# elasticNode.net
KiCad netlist of a schematic drawn in EAGLE
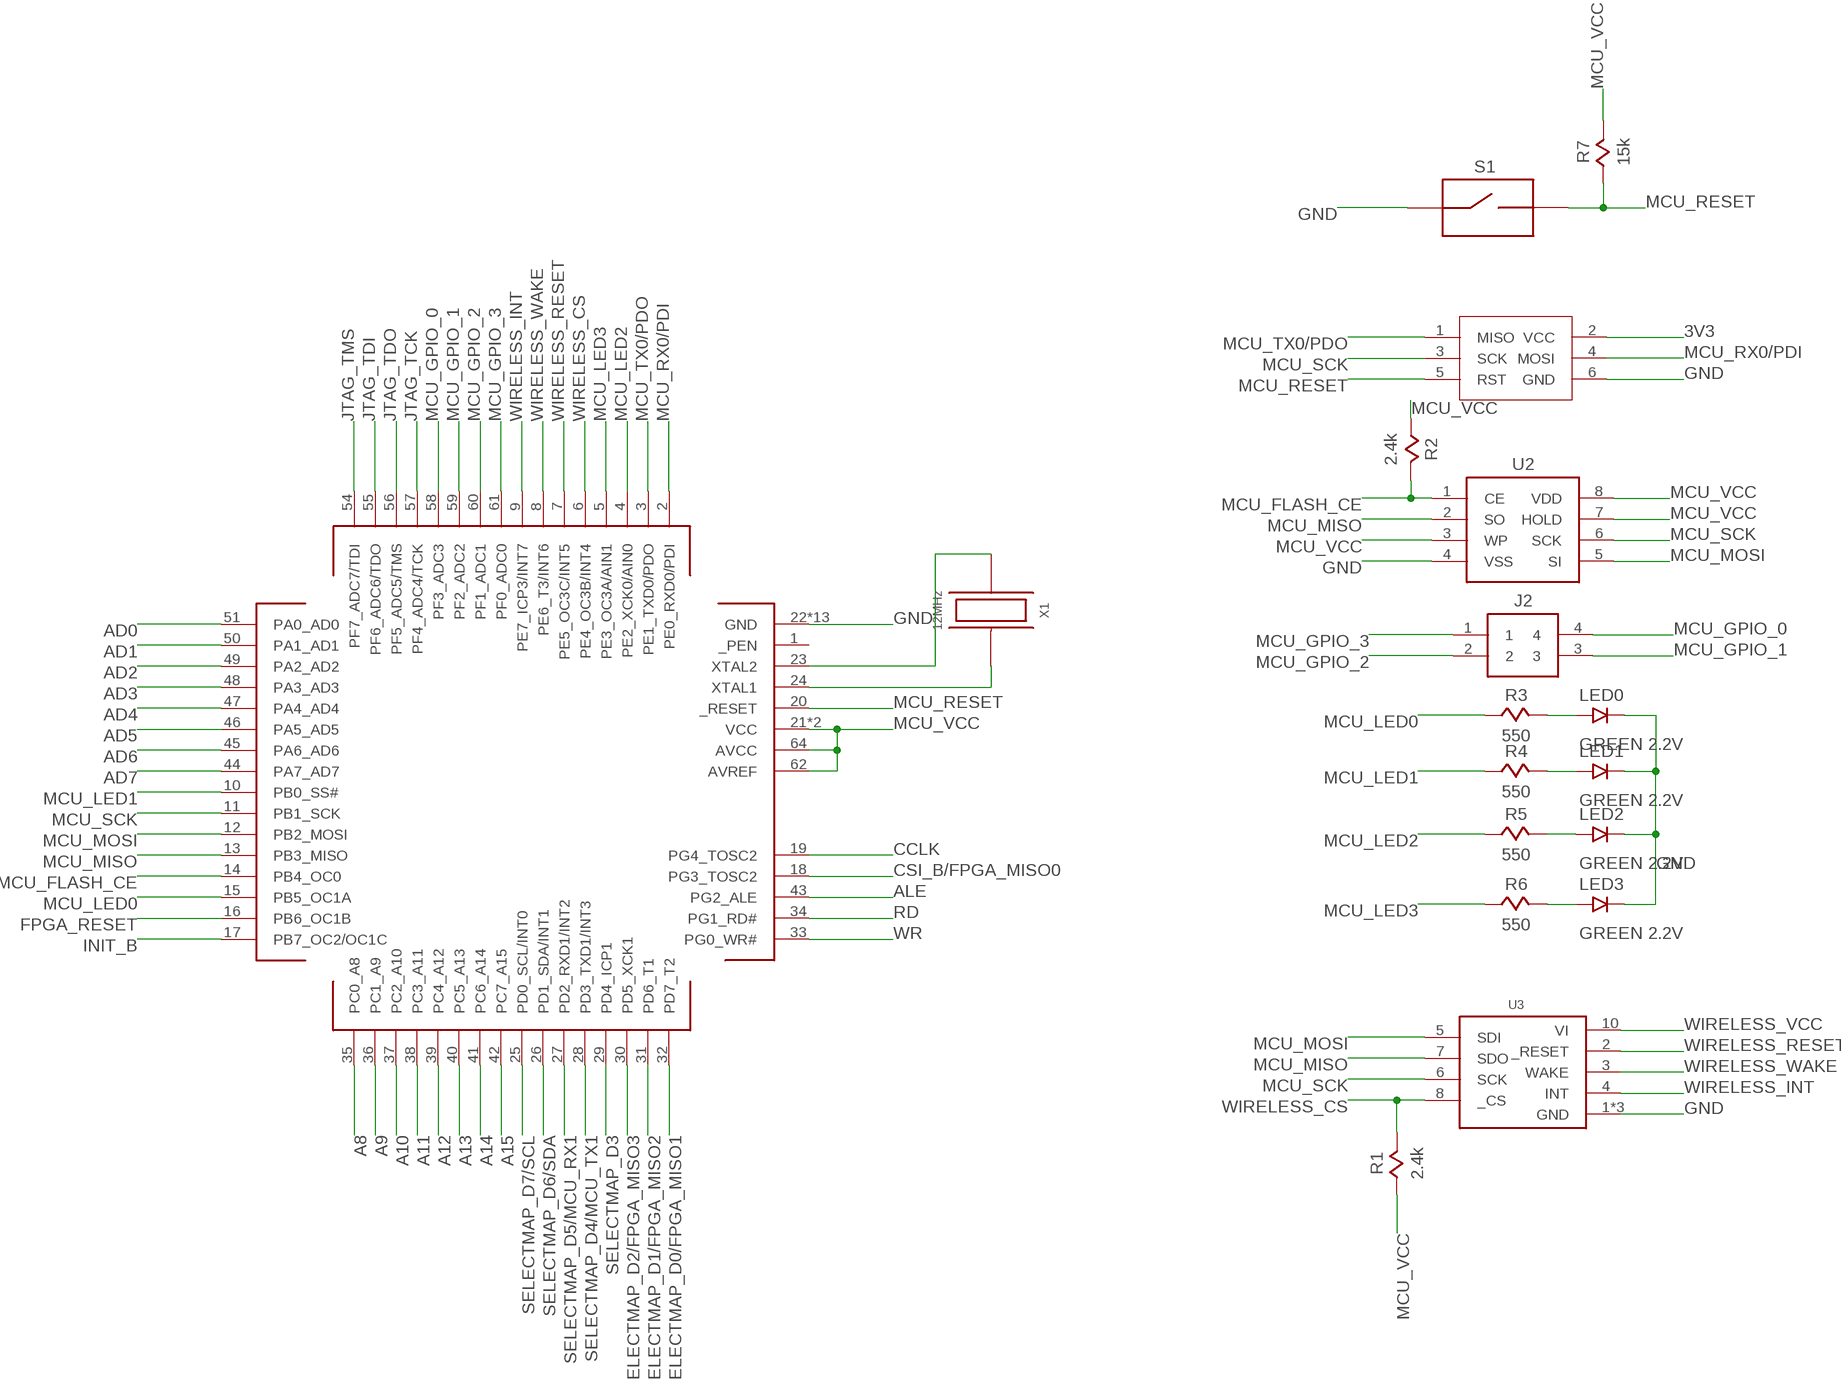
[diagram p0: schematic, sheet 1]
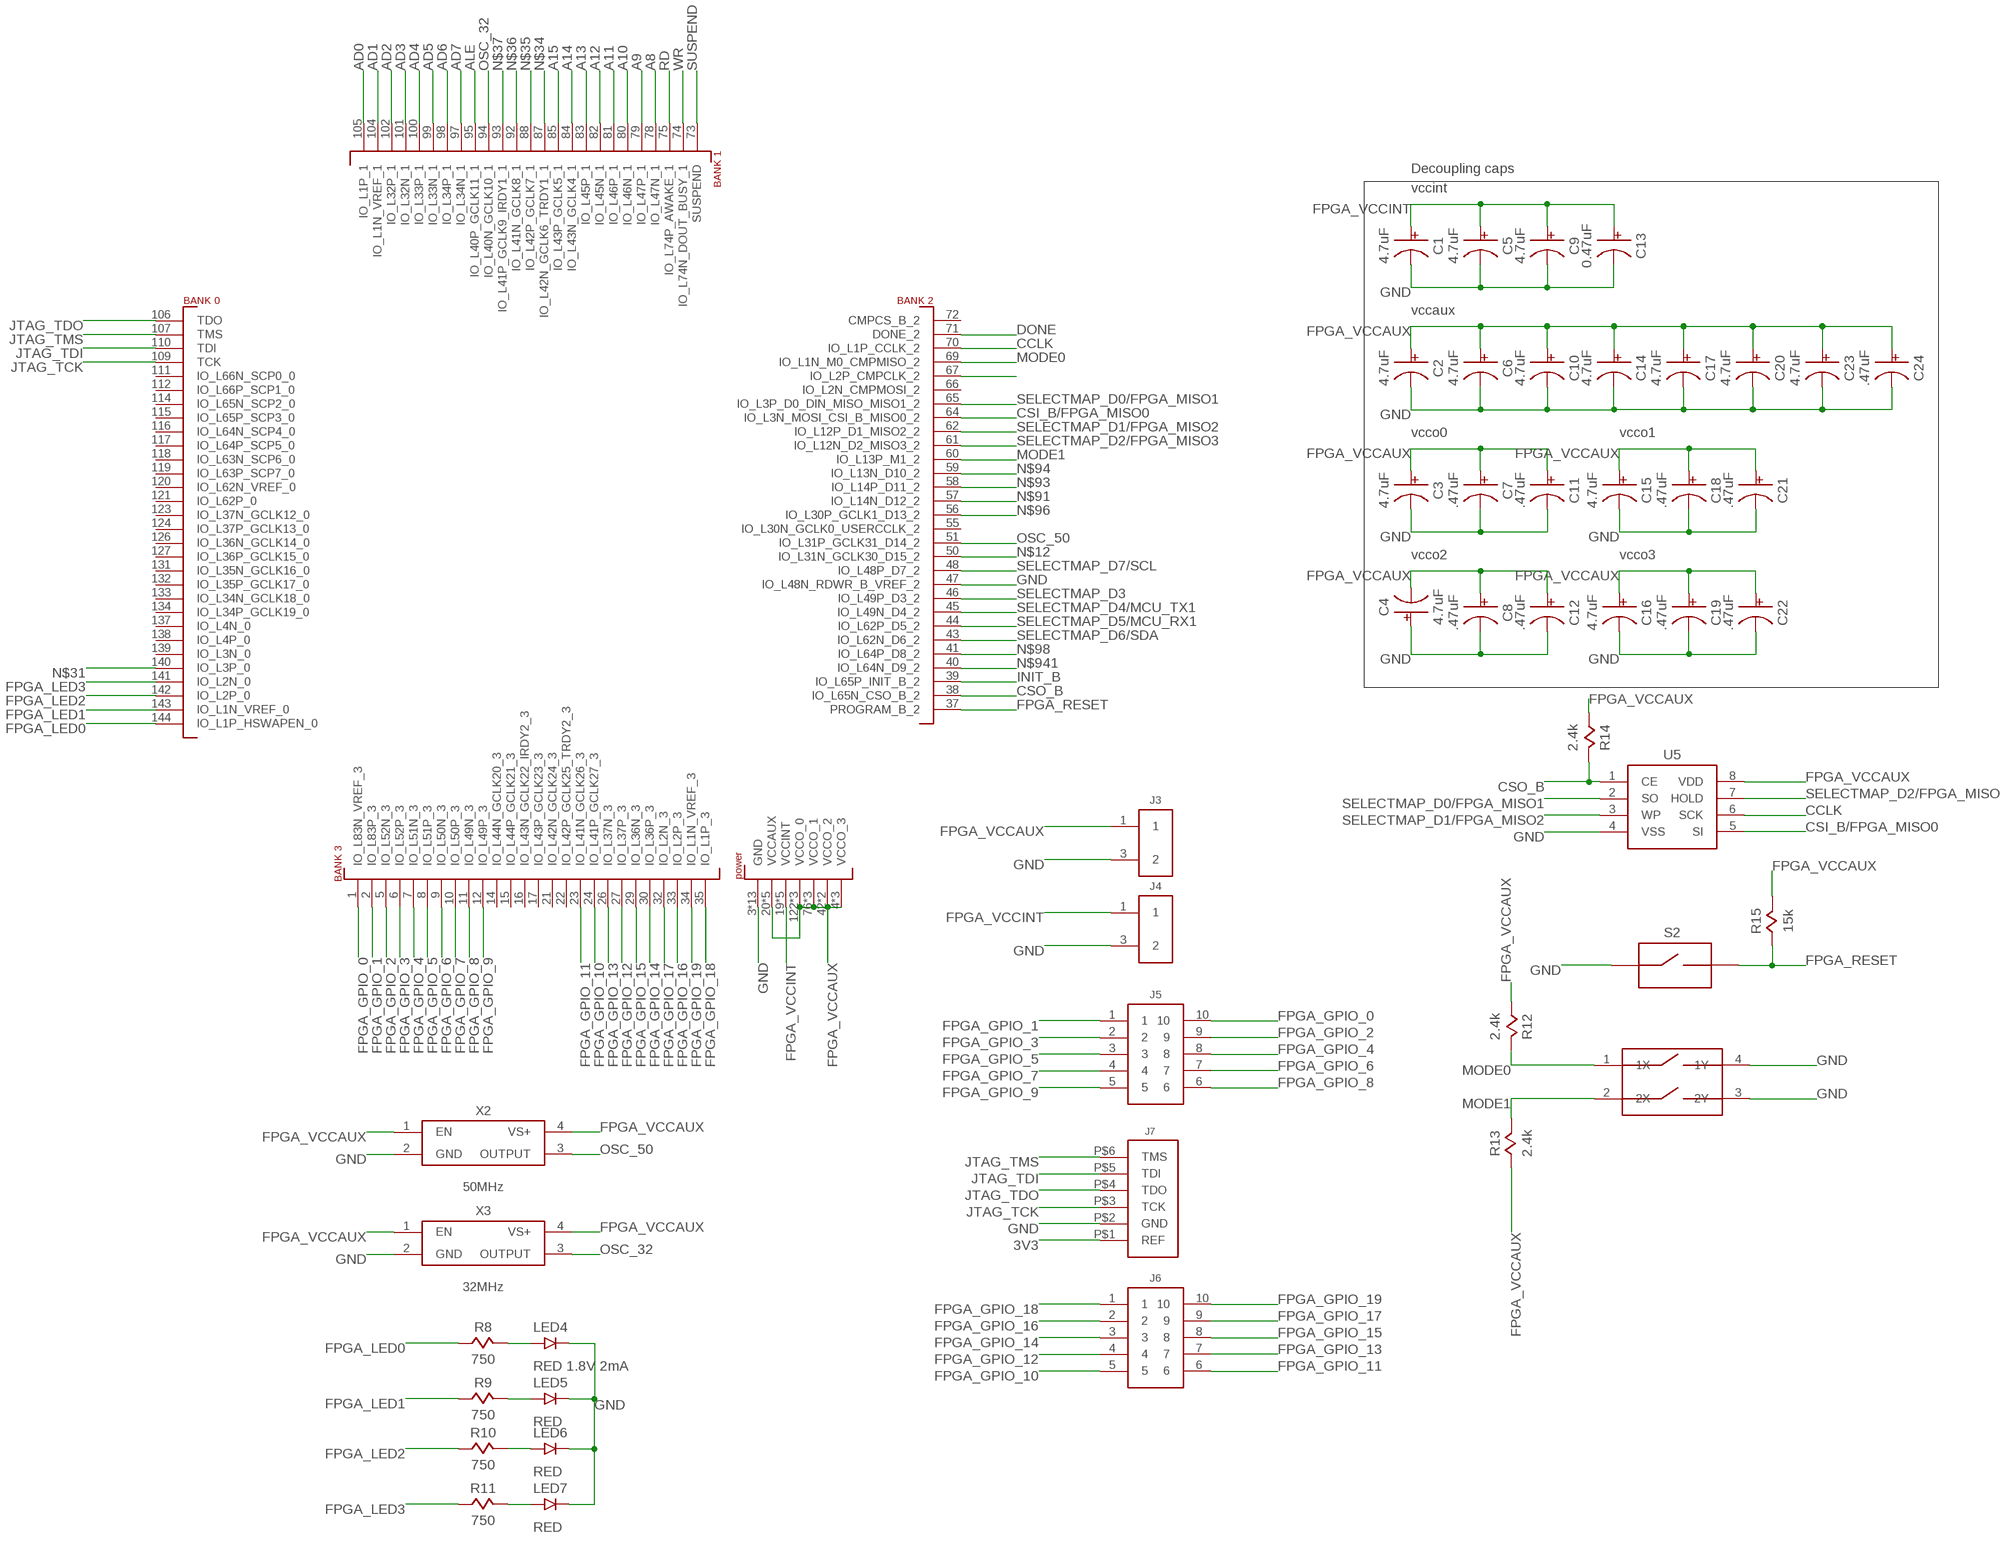
[diagram p1: schematic, sheet 2]
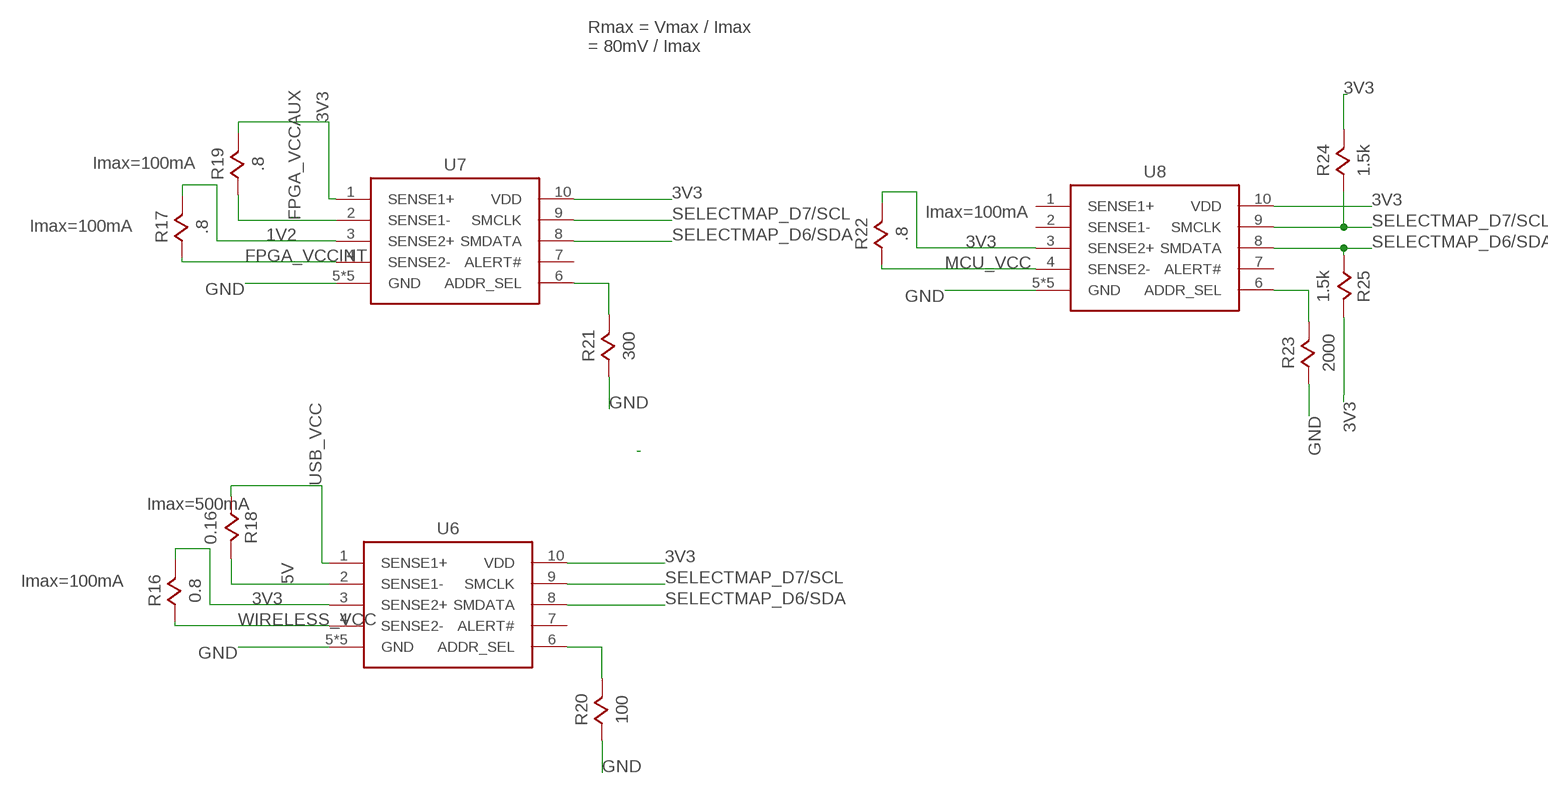
[diagram p2: schematic, sheet 3]
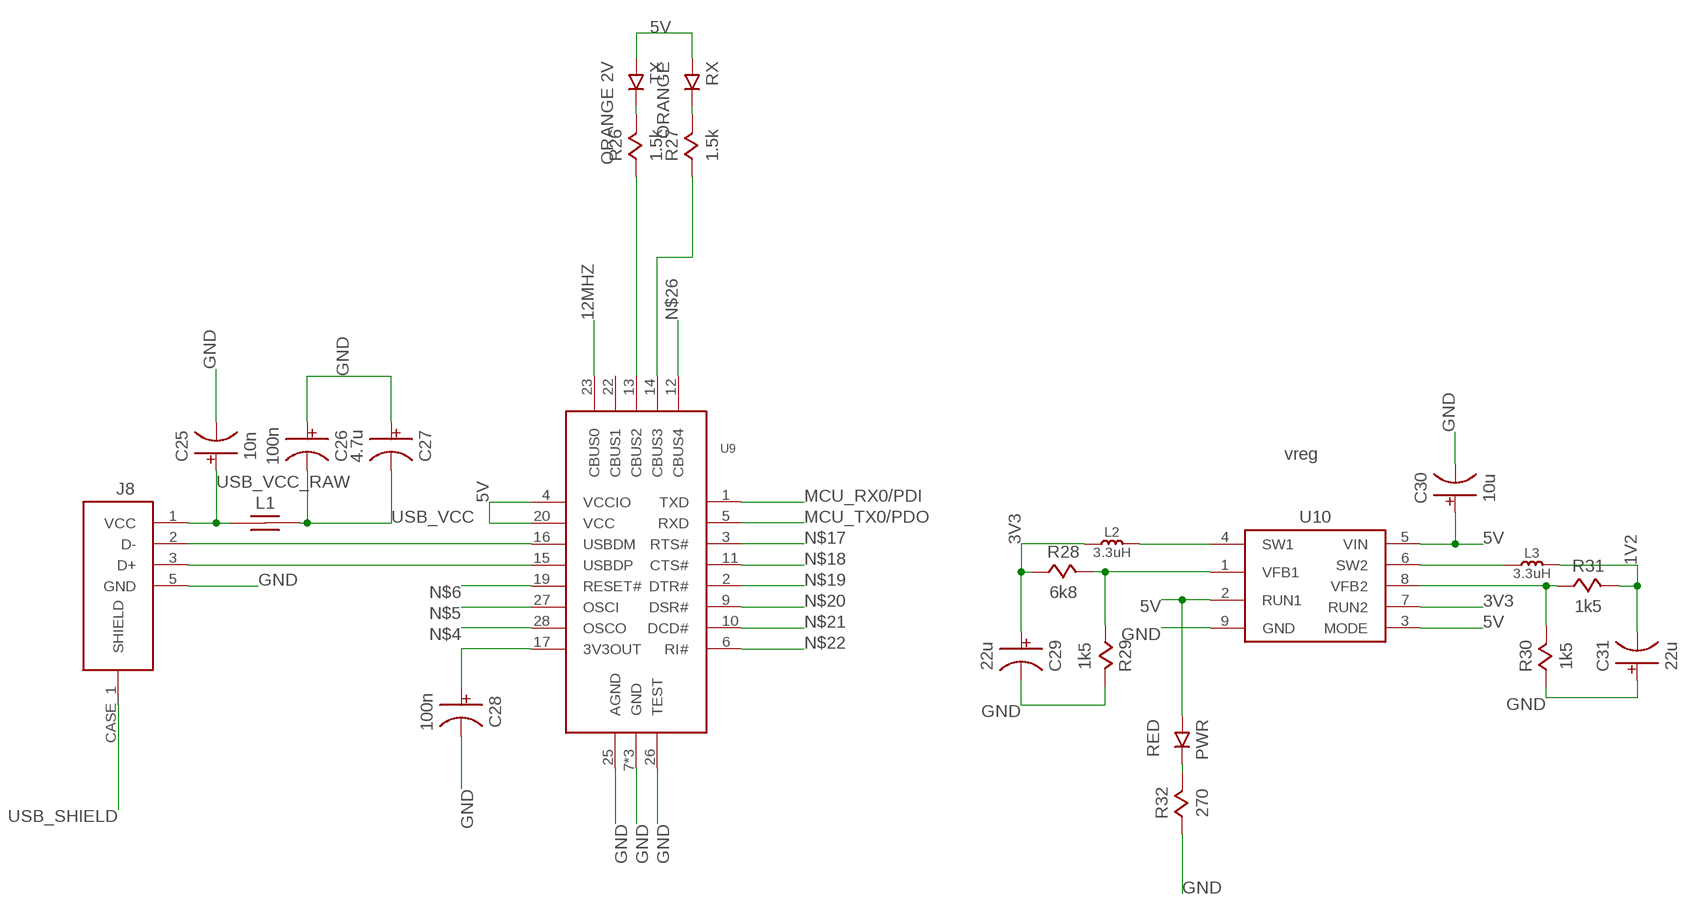
[diagram p3: schematic, sheet 4]

(export (version "E")
  (design (tool "Eeschema 10.0.6"))
  (components
    (comp (ref "R16")
      (value "0.8")
      (footprint "eagle-import:0805")
      (libsource (lib "eagle-import") (part "RESISTOR"))
    )
    (comp (ref "R17")
      (value ".8")
      (footprint "eagle-import:0805")
      (libsource (lib "eagle-import") (part "RESISTOR"))
    )
    (comp (ref "R18")
      (value "0.16")
      (footprint "eagle-import:0805")
      (libsource (lib "eagle-import") (part "RESISTOR"))
    )
    (comp (ref "R19")
      (value ".8")
      (footprint "eagle-import:0805")
      (libsource (lib "eagle-import") (part "RESISTOR"))
    )
    (comp (ref "R20")
      (value "100")
      (footprint "eagle-import:0805")
      (libsource (lib "eagle-import") (part "RESISTOR"))
    )
    (comp (ref "R21")
      (value "300")
      (footprint "eagle-import:0805")
      (libsource (lib "eagle-import") (part "RESISTOR"))
    )
    (comp (ref "R22")
      (value ".8")
      (footprint "eagle-import:0805")
      (libsource (lib "eagle-import") (part "RESISTOR"))
    )
    (comp (ref "R23")
      (value "2000")
      (footprint "eagle-import:0805")
      (libsource (lib "eagle-import") (part "RESISTOR"))
    )
    (comp (ref "R24")
      (value "1.5k")
      (footprint "eagle-import:0805")
      (libsource (lib "eagle-import") (part "RESISTOR"))
    )
    (comp (ref "R25")
      (value "1.5k")
      (footprint "eagle-import:0805")
      (libsource (lib "eagle-import") (part "RESISTOR"))
    )
    (comp (ref "U6")
      (value "PAC1720")
      (footprint "eagle-import:VDFN10")
      (libsource (lib "eagle-import") (part "PAC1720"))
    )
    (comp (ref "U7")
      (value "PAC1720")
      (footprint "eagle-import:VDFN10")
      (libsource (lib "eagle-import") (part "PAC1720"))
    )
    (comp (ref "U8")
      (value "PAC1720")
      (footprint "eagle-import:VDFN10")
      (libsource (lib "eagle-import") (part "PAC1720"))
    )
    (comp (ref "J1")
      (value "ISP_CONN_6PIN")
      (footprint "eagle-import:3X2_HEADER_SMT")
      (libsource (lib "eagle-import") (part "ISP_CONN_6PIN"))
    )
    (comp (ref "J2")
      (value "FEMALE_HEADER_2X2")
      (footprint "eagle-import:2X2_HEADER")
      (libsource (lib "eagle-import") (part "FEMALE_HEADER_2X2"))
    )
    (comp (ref "LED0")
      (value "GREEN 2.2V")
      (footprint "eagle-import:0805")
      (libsource (lib "eagle-import") (part "LED"))
    )
    (comp (ref "LED1")
      (value "GREEN 2.2V")
      (footprint "eagle-import:0805")
      (libsource (lib "eagle-import") (part "LED"))
    )
    (comp (ref "LED2")
      (value "GREEN 2.2V")
      (footprint "eagle-import:0805")
      (libsource (lib "eagle-import") (part "LED"))
    )
    (comp (ref "LED3")
      (value "GREEN 2.2V")
      (footprint "eagle-import:0805")
      (libsource (lib "eagle-import") (part "LED"))
    )
    (comp (ref "R1")
      (value "2.4k")
      (footprint "eagle-import:0805")
      (libsource (lib "eagle-import") (part "RESISTOR"))
    )
    (comp (ref "R2")
      (value "2.4k")
      (footprint "eagle-import:0805")
      (libsource (lib "eagle-import") (part "RESISTOR"))
    )
    (comp (ref "R3")
      (value "550")
      (footprint "eagle-import:0805")
      (libsource (lib "eagle-import") (part "RESISTOR"))
    )
    (comp (ref "R4")
      (value "550")
      (footprint "eagle-import:0805")
      (libsource (lib "eagle-import") (part "RESISTOR"))
    )
    (comp (ref "R5")
      (value "550")
      (footprint "eagle-import:0805")
      (libsource (lib "eagle-import") (part "RESISTOR"))
    )
    (comp (ref "R6")
      (value "550")
      (footprint "eagle-import:0805")
      (libsource (lib "eagle-import") (part "RESISTOR"))
    )
    (comp (ref "R7")
      (value "15k")
      (footprint "eagle-import:0805")
      (libsource (lib "eagle-import") (part "RESISTOR"))
    )
    (comp (ref "S1")
      (value "SPST_BUTTON2PIN_SMT")
      (footprint "eagle-import:SPST_2PIN_SMT")
      (libsource (lib "eagle-import") (part "SPST_BUTTON2PIN_SMT"))
    )
    (comp (ref "U1")
      (value "ATMEGA64AQFN")
      (footprint "eagle-import:QFN64")
      (libsource (lib "eagle-import") (part "ATMEGA64AQFN"))
    )
    (comp (ref "U2")
      (value "SST26VF032B")
      (footprint "eagle-import:SOIC8")
      (libsource (lib "eagle-import") (part "SST26VF032B"))
    )
    (comp (ref "U3")
      (value "MRF24J40MA")
      (footprint "eagle-import:MRF24J40MA")
      (libsource (lib "eagle-import") (part "MRF24J40MA"))
    )
    (comp (ref "X1")
      (value "12MHz")
      (footprint "eagle-import:3.2X2.5_OSC")
      (libsource (lib "eagle-import") (part "QUARTZ"))
    )
    (comp (ref "C25")
      (value "10n")
      (footprint "eagle-import:0805")
      (libsource (lib "eagle-import") (part "CAPACITOR0805"))
    )
    (comp (ref "C26")
      (value "100n")
      (footprint "eagle-import:0805")
      (libsource (lib "eagle-import") (part "CAPACITOR0805"))
    )
    (comp (ref "C27")
      (value "4.7u")
      (footprint "eagle-import:0805")
      (libsource (lib "eagle-import") (part "CAPACITOR0805"))
    )
    (comp (ref "C28")
      (value "100n")
      (footprint "eagle-import:0805")
      (libsource (lib "eagle-import") (part "CAPACITOR0805"))
    )
    (comp (ref "C29")
      (value "22u")
      (footprint "eagle-import:0805")
      (libsource (lib "eagle-import") (part "CAPACITOR0805"))
    )
    (comp (ref "C30")
      (value "10u")
      (footprint "eagle-import:0805")
      (libsource (lib "eagle-import") (part "CAPACITOR0805"))
    )
    (comp (ref "C31")
      (value "22u")
      (footprint "eagle-import:0805")
      (libsource (lib "eagle-import") (part "CAPACITOR0805"))
    )
    (comp (ref "J8")
      (value "USB_CONNSMT")
      (footprint "eagle-import:USB_MICRO_B_SMT")
      (libsource (lib "eagle-import") (part "USB_CONNSMT"))
    )
    (comp (ref "L1")
      (value "40Ohm 1.5A")
      (footprint "eagle-import:0805")
      (libsource (lib "eagle-import") (part "FERRITE_BEAD"))
    )
    (comp (ref "L2")
      (value "3.3uH")
      (footprint "eagle-import:0805")
      (libsource (lib "eagle-import") (part "INDUCTOR"))
    )
    (comp (ref "L3")
      (value "3.3uH")
      (footprint "eagle-import:0805")
      (libsource (lib "eagle-import") (part "INDUCTOR"))
    )
    (comp (ref "PWR")
      (value "RED")
      (footprint "eagle-import:0805")
      (libsource (lib "eagle-import") (part "LED"))
    )
    (comp (ref "R26")
      (value "1.5k")
      (footprint "eagle-import:0805")
      (libsource (lib "eagle-import") (part "RESISTOR"))
    )
    (comp (ref "R27")
      (value "1.5k")
      (footprint "eagle-import:0805")
      (libsource (lib "eagle-import") (part "RESISTOR"))
    )
    (comp (ref "R28")
      (value "6k8")
      (footprint "eagle-import:0805")
      (libsource (lib "eagle-import") (part "RESISTOR"))
    )
    (comp (ref "R29")
      (value "1k5")
      (footprint "eagle-import:0805")
      (libsource (lib "eagle-import") (part "RESISTOR"))
    )
    (comp (ref "R30")
      (value "1k5")
      (footprint "eagle-import:0805")
      (libsource (lib "eagle-import") (part "RESISTOR"))
    )
    (comp (ref "R31")
      (value "1k5")
      (footprint "eagle-import:0805")
      (libsource (lib "eagle-import") (part "RESISTOR"))
    )
    (comp (ref "R32")
      (value "270")
      (footprint "eagle-import:0805")
      (libsource (lib "eagle-import") (part "RESISTOR"))
    )
    (comp (ref "RX")
      (value "ORANGE")
      (footprint "eagle-import:0805")
      (libsource (lib "eagle-import") (part "LED"))
    )
    (comp (ref "TX")
      (value "ORANGE 2V")
      (footprint "eagle-import:0805")
      (libsource (lib "eagle-import") (part "LED"))
    )
    (comp (ref "U9")
      (value "FT232RSSOP28")
      (footprint "eagle-import:SSOP28")
      (libsource (lib "eagle-import") (part "FT232RSSOP28"))
    )
    (comp (ref "U10")
      (value "LTC3419DFN")
      (footprint "eagle-import:DFN8")
      (libsource (lib "eagle-import") (part "LTC3419DFN"))
    )
    (comp (ref "C1")
      (value "4.7uF")
      (footprint "eagle-import:0805")
      (libsource (lib "eagle-import") (part "CAPACITOR0805"))
    )
    (comp (ref "C2")
      (value "4.7uF")
      (footprint "eagle-import:0805")
      (libsource (lib "eagle-import") (part "CAPACITOR0805"))
    )
    (comp (ref "C3")
      (value "4.7uF")
      (footprint "eagle-import:0805")
      (libsource (lib "eagle-import") (part "CAPACITOR0805"))
    )
    (comp (ref "C4")
      (value "4.7uF")
      (footprint "eagle-import:0805")
      (libsource (lib "eagle-import") (part "CAPACITOR0805"))
    )
    (comp (ref "C5")
      (value "4.7uF")
      (footprint "eagle-import:0805")
      (libsource (lib "eagle-import") (part "CAPACITOR0805"))
    )
    (comp (ref "C6")
      (value "4.7uF")
      (footprint "eagle-import:0805")
      (libsource (lib "eagle-import") (part "CAPACITOR0805"))
    )
    (comp (ref "C7")
      (value ".47uF")
      (footprint "eagle-import:0402")
      (libsource (lib "eagle-import") (part "CAPACITOR0402"))
    )
    (comp (ref "C8")
      (value ".47uF")
      (footprint "eagle-import:0402")
      (libsource (lib "eagle-import") (part "CAPACITOR0402"))
    )
    (comp (ref "C9")
      (value "4.7uF")
      (footprint "eagle-import:0805")
      (libsource (lib "eagle-import") (part "CAPACITOR0805"))
    )
    (comp (ref "C10")
      (value "4.7uF")
      (footprint "eagle-import:0805")
      (libsource (lib "eagle-import") (part "CAPACITOR0805"))
    )
    (comp (ref "C11")
      (value ".47uF")
      (footprint "eagle-import:0402")
      (libsource (lib "eagle-import") (part "CAPACITOR0402"))
    )
    (comp (ref "C12")
      (value ".47uF")
      (footprint "eagle-import:0402")
      (libsource (lib "eagle-import") (part "CAPACITOR0402"))
    )
    (comp (ref "C13")
      (value "0.47uF")
      (footprint "eagle-import:0402")
      (libsource (lib "eagle-import") (part "CAPACITOR0402"))
    )
    (comp (ref "C14")
      (value "4.7uF")
      (footprint "eagle-import:0805")
      (libsource (lib "eagle-import") (part "CAPACITOR0805"))
    )
    (comp (ref "C15")
      (value "4.7uF")
      (footprint "eagle-import:0805")
      (libsource (lib "eagle-import") (part "CAPACITOR0805"))
    )
    (comp (ref "C16")
      (value "4.7uF")
      (footprint "eagle-import:0805")
      (libsource (lib "eagle-import") (part "CAPACITOR0805"))
    )
    (comp (ref "C17")
      (value "4.7uF")
      (footprint "eagle-import:0805")
      (libsource (lib "eagle-import") (part "CAPACITOR0805"))
    )
    (comp (ref "C18")
      (value ".47uF")
      (footprint "eagle-import:0402")
      (libsource (lib "eagle-import") (part "CAPACITOR0402"))
    )
    (comp (ref "C19")
      (value ".47uF")
      (footprint "eagle-import:0402")
      (libsource (lib "eagle-import") (part "CAPACITOR0402"))
    )
    (comp (ref "C20")
      (value "4.7uF")
      (footprint "eagle-import:0805")
      (libsource (lib "eagle-import") (part "CAPACITOR0805"))
    )
    (comp (ref "C21")
      (value ".47uF")
      (footprint "eagle-import:0402")
      (libsource (lib "eagle-import") (part "CAPACITOR0402"))
    )
    (comp (ref "C22")
      (value ".47uF")
      (footprint "eagle-import:0402")
      (libsource (lib "eagle-import") (part "CAPACITOR0402"))
    )
    (comp (ref "C23")
      (value "4.7uF")
      (footprint "eagle-import:0805")
      (libsource (lib "eagle-import") (part "CAPACITOR0805"))
    )
    (comp (ref "C24")
      (value ".47uF")
      (footprint "eagle-import:0805")
      (libsource (lib "eagle-import") (part "CAPACITOR0805"))
    )
    (comp (ref "J3")
      (value "FEMALE_HEADER_2X1")
      (footprint "eagle-import:2X1_HEADER")
      (libsource (lib "eagle-import") (part "FEMALE_HEADER_2X1"))
    )
    (comp (ref "J4")
      (value "FEMALE_HEADER_2X1")
      (footprint "eagle-import:2X1_HEADER")
      (libsource (lib "eagle-import") (part "FEMALE_HEADER_2X1"))
    )
    (comp (ref "J5")
      (value "FEMALE_HEADER_5X2")
      (footprint "eagle-import:5X2_HEADER")
      (libsource (lib "eagle-import") (part "FEMALE_HEADER_5X2"))
    )
    (comp (ref "J6")
      (value "FEMALE_HEADER_5X2")
      (footprint "eagle-import:5X2_HEADER")
      (libsource (lib "eagle-import") (part "FEMALE_HEADER_5X2"))
    )
    (comp (ref "J7")
      (value "JTAG_CONN_6PINTHT")
      (footprint "eagle-import:6X1_HEADER")
      (libsource (lib "eagle-import") (part "JTAG_CONN_6PINTHT"))
    )
    (comp (ref "LED4")
      (value "RED 1.8V 2mA")
      (footprint "eagle-import:0805")
      (libsource (lib "eagle-import") (part "LED"))
    )
    (comp (ref "LED5")
      (value "RED")
      (footprint "eagle-import:0805")
      (libsource (lib "eagle-import") (part "LED"))
    )
    (comp (ref "LED6")
      (value "RED")
      (footprint "eagle-import:0805")
      (libsource (lib "eagle-import") (part "LED"))
    )
    (comp (ref "LED7")
      (value "RED")
      (footprint "eagle-import:0805")
      (libsource (lib "eagle-import") (part "LED"))
    )
    (comp (ref "R8")
      (value "750")
      (footprint "eagle-import:0805")
      (libsource (lib "eagle-import") (part "RESISTOR"))
    )
    (comp (ref "R9")
      (value "750")
      (footprint "eagle-import:0805")
      (libsource (lib "eagle-import") (part "RESISTOR"))
    )
    (comp (ref "R10")
      (value "750")
      (footprint "eagle-import:0805")
      (libsource (lib "eagle-import") (part "RESISTOR"))
    )
    (comp (ref "R11")
      (value "750")
      (footprint "eagle-import:0805")
      (libsource (lib "eagle-import") (part "RESISTOR"))
    )
    (comp (ref "R12")
      (value "2.4k")
      (footprint "eagle-import:0805")
      (libsource (lib "eagle-import") (part "RESISTOR"))
    )
    (comp (ref "R13")
      (value "2.4k")
      (footprint "eagle-import:0805")
      (libsource (lib "eagle-import") (part "RESISTOR"))
    )
    (comp (ref "R14")
      (value "2.4k")
      (footprint "eagle-import:0805")
      (libsource (lib "eagle-import") (part "RESISTOR"))
    )
    (comp (ref "R15")
      (value "15k")
      (footprint "eagle-import:0805")
      (libsource (lib "eagle-import") (part "RESISTOR"))
    )
    (comp (ref "S2")
      (value "SPST_BUTTON2PIN_SMT")
      (footprint "eagle-import:SPST_2PIN_SMT")
      (libsource (lib "eagle-import") (part "SPST_BUTTON2PIN_SMT"))
    )
    (comp (ref "S3")
      (value "SPST_DIP_2SMT")
      (footprint "eagle-import:SPST_DIP2_SMT")
      (libsource (lib "eagle-import") (part "SPST_DIP_2SMT"))
    )
    (comp (ref "U4")
      (value "SPARTAN6-LX9")
      (footprint "eagle-import:TQG144")
      (libsource (lib "eagle-import") (part "SPARTAN6-LX9"))
    )
    (comp (ref "U5")
      (value "SST26VF032B")
      (footprint "eagle-import:SOIC8")
      (libsource (lib "eagle-import") (part "SST26VF032B"))
    )
    (comp (ref "X2")
      (value "50MHz")
      (footprint "eagle-import:3.2X2.5_OSC")
      (libsource (lib "eagle-import") (part "OSCILLATOR3.2X2.5"))
    )
    (comp (ref "X3")
      (value "32MHz")
      (footprint "eagle-import:3.2X2.5_OSC")
      (libsource (lib "eagle-import") (part "OSCILLATOR3.2X2.5"))
    )
  )
  (nets
    (net (code "1") (name "1V2") (class "Default")
      (node (ref "C31") (pin "2") (pinfunction "P$2_2") (pintype "bidirectional"))
      (node (ref "L3") (pin "2") (pinfunction "P$2_2") (pintype "bidirectional"))
      (node (ref "R17") (pin "2") (pinfunction "2_2") (pintype "bidirectional"))
      (node (ref "R31") (pin "2") (pinfunction "2_2") (pintype "bidirectional"))
      (node (ref "U7") (pin "3") (pinfunction "SENSE2+_3") (pintype "bidirectional"))
    )
    (net (code "2") (name "3V3") (class "Default")
      (node (ref "C29") (pin "1") (pinfunction "P$1_1") (pintype "bidirectional"))
      (node (ref "J1") (pin "2") (pinfunction "VCC_2") (pintype "bidirectional"))
      (node (ref "J7") (pin "P$1") (pinfunction "REF_P$1") (pintype "bidirectional"))
      (node (ref "L2") (pin "1") (pinfunction "P$1_1") (pintype "bidirectional"))
      (node (ref "R16") (pin "2") (pinfunction "2_2") (pintype "bidirectional"))
      (node (ref "R19") (pin "2") (pinfunction "2_2") (pintype "bidirectional"))
      (node (ref "R22") (pin "2") (pinfunction "2_2") (pintype "bidirectional"))
      (node (ref "R24") (pin "2") (pinfunction "2_2") (pintype "bidirectional"))
      (node (ref "R25") (pin "2") (pinfunction "2_2") (pintype "bidirectional"))
      (node (ref "R28") (pin "1") (pinfunction "1_1") (pintype "bidirectional"))
      (node (ref "U10") (pin "7") (pinfunction "RUN2_7") (pintype "bidirectional"))
      (node (ref "U6") (pin "10") (pinfunction "VDD_10") (pintype "bidirectional"))
      (node (ref "U6") (pin "3") (pinfunction "SENSE2+_3") (pintype "bidirectional"))
      (node (ref "U7") (pin "1") (pinfunction "SENSE1+_1") (pintype "bidirectional"))
      (node (ref "U7") (pin "10") (pinfunction "VDD_10") (pintype "bidirectional"))
      (node (ref "U8") (pin "10") (pinfunction "VDD_10") (pintype "bidirectional"))
      (node (ref "U8") (pin "3") (pinfunction "SENSE2+_3") (pintype "bidirectional"))
    )
    (net (code "3") (name "5V") (class "Default")
      (node (ref "C30") (pin "1") (pinfunction "P$1_1") (pintype "bidirectional"))
      (node (ref "PWR") (pin "1") (pinfunction "1_1") (pintype "bidirectional"))
      (node (ref "R18") (pin "2") (pinfunction "2_2") (pintype "bidirectional"))
      (node (ref "RX") (pin "1") (pinfunction "1_1") (pintype "bidirectional"))
      (node (ref "TX") (pin "1") (pinfunction "1_1") (pintype "bidirectional"))
      (node (ref "U10") (pin "2") (pinfunction "RUN1_2") (pintype "bidirectional"))
      (node (ref "U10") (pin "3") (pinfunction "MODE_3") (pintype "bidirectional"))
      (node (ref "U10") (pin "5") (pinfunction "VIN_5") (pintype "bidirectional"))
      (node (ref "U6") (pin "2") (pinfunction "SENSE1-_2") (pintype "bidirectional"))
      (node (ref "U9") (pin "20") (pinfunction "VCC_20") (pintype "bidirectional"))
      (node (ref "U9") (pin "4") (pinfunction "VCCIO_4") (pintype "bidirectional"))
    )
    (net (code "4") (name "12MHZ") (class "Default")
      (node (ref "U9") (pin "23") (pinfunction "CBUS0_23") (pintype "bidirectional"))
    )
    (net (code "5") (name "A8") (class "Default")
      (node (ref "U1") (pin "35") (pinfunction "PC0_A8_35") (pintype "bidirectional"))
      (node (ref "U4") (pin "78") (pinfunction "IO_L47N_1_78") (pintype "bidirectional"))
    )
    (net (code "6") (name "A9") (class "Default")
      (node (ref "U1") (pin "36") (pinfunction "PC1_A9_36") (pintype "bidirectional"))
      (node (ref "U4") (pin "79") (pinfunction "IO_L47P_1_79") (pintype "bidirectional"))
    )
    (net (code "7") (name "A10") (class "Default")
      (node (ref "U1") (pin "37") (pinfunction "PC2_A10_37") (pintype "bidirectional"))
      (node (ref "U4") (pin "80") (pinfunction "IO_L46N_1_80") (pintype "bidirectional"))
    )
    (net (code "8") (name "A11") (class "Default")
      (node (ref "U1") (pin "38") (pinfunction "PC3_A11_38") (pintype "bidirectional"))
      (node (ref "U4") (pin "81") (pinfunction "IO_L46P_1_81") (pintype "bidirectional"))
    )
    (net (code "9") (name "A12") (class "Default")
      (node (ref "U1") (pin "39") (pinfunction "PC4_A12_39") (pintype "bidirectional"))
      (node (ref "U4") (pin "82") (pinfunction "IO_L45N_1_82") (pintype "bidirectional"))
    )
    (net (code "10") (name "A13") (class "Default")
      (node (ref "U1") (pin "40") (pinfunction "PC5_A13_40") (pintype "bidirectional"))
      (node (ref "U4") (pin "83") (pinfunction "IO_L45P_1_83") (pintype "bidirectional"))
    )
    (net (code "11") (name "A14") (class "Default")
      (node (ref "U1") (pin "41") (pinfunction "PC6_A14_41") (pintype "bidirectional"))
      (node (ref "U4") (pin "84") (pinfunction "IO_L43N_GCLK4_1_84") (pintype "bidirectional"))
    )
    (net (code "12") (name "A15") (class "Default")
      (node (ref "U1") (pin "42") (pinfunction "PC7_A15_42") (pintype "bidirectional"))
      (node (ref "U4") (pin "85") (pinfunction "IO_L43P_GCLK5_1_85") (pintype "bidirectional"))
    )
    (net (code "13") (name "AD0") (class "Default")
      (node (ref "U1") (pin "51") (pinfunction "PA0_AD0_51") (pintype "bidirectional"))
      (node (ref "U4") (pin "105") (pinfunction "IO_L1P_1_105") (pintype "bidirectional"))
    )
    (net (code "14") (name "AD1") (class "Default")
      (node (ref "U1") (pin "50") (pinfunction "PA1_AD1_50") (pintype "bidirectional"))
      (node (ref "U4") (pin "104") (pinfunction "IO_L1N_VREF_1_104") (pintype "bidirectional"))
    )
    (net (code "15") (name "AD2") (class "Default")
      (node (ref "U1") (pin "49") (pinfunction "PA2_AD2_49") (pintype "bidirectional"))
      (node (ref "U4") (pin "102") (pinfunction "IO_L32P_1_102") (pintype "bidirectional"))
    )
    (net (code "16") (name "AD3") (class "Default")
      (node (ref "U1") (pin "48") (pinfunction "PA3_AD3_48") (pintype "bidirectional"))
      (node (ref "U4") (pin "101") (pinfunction "IO_L32N_1_101") (pintype "bidirectional"))
    )
    (net (code "17") (name "AD4") (class "Default")
      (node (ref "U1") (pin "47") (pinfunction "PA4_AD4_47") (pintype "bidirectional"))
      (node (ref "U4") (pin "100") (pinfunction "IO_L33P_1_100") (pintype "bidirectional"))
    )
    (net (code "18") (name "AD5") (class "Default")
      (node (ref "U1") (pin "46") (pinfunction "PA5_AD5_46") (pintype "bidirectional"))
      (node (ref "U4") (pin "99") (pinfunction "IO_L33N_1_99") (pintype "bidirectional"))
    )
    (net (code "19") (name "AD6") (class "Default")
      (node (ref "U1") (pin "45") (pinfunction "PA6_AD6_45") (pintype "bidirectional"))
      (node (ref "U4") (pin "98") (pinfunction "IO_L34P_1_98") (pintype "bidirectional"))
    )
    (net (code "20") (name "AD7") (class "Default")
      (node (ref "U1") (pin "44") (pinfunction "PA7_AD7_44") (pintype "bidirectional"))
      (node (ref "U4") (pin "97") (pinfunction "IO_L34N_1_97") (pintype "bidirectional"))
    )
    (net (code "21") (name "ALE") (class "Default")
      (node (ref "U1") (pin "43") (pinfunction "PG2_ALE_43") (pintype "bidirectional"))
      (node (ref "U4") (pin "95") (pinfunction "IO_L40P_GCLK11_1_95") (pintype "bidirectional"))
    )
    (net (code "22") (name "CCLK") (class "Default")
      (node (ref "U1") (pin "19") (pinfunction "PG4_TOSC2_19") (pintype "bidirectional"))
      (node (ref "U4") (pin "70") (pinfunction "IO_L1P_CCLK_2_70") (pintype "bidirectional"))
      (node (ref "U5") (pin "6") (pinfunction "SCK_6") (pintype "bidirectional"))
    )
    (net (code "23") (name "CSI_B{slash}FPGA_MISO0") (class "Default")
      (node (ref "U1") (pin "18") (pinfunction "PG3_TOSC2_18") (pintype "bidirectional"))
      (node (ref "U4") (pin "64") (pinfunction "IO_L3N_MOSI_CSI_B_MISO0_2_64") (pintype "bidirectional"))
      (node (ref "U5") (pin "5") (pinfunction "SI_5") (pintype "bidirectional"))
    )
    (net (code "24") (name "CSO_B") (class "Default")
      (node (ref "R14") (pin "2") (pinfunction "2_2") (pintype "bidirectional"))
      (node (ref "U4") (pin "38") (pinfunction "IO_L65N_CSO_B_2_38") (pintype "bidirectional"))
      (node (ref "U5") (pin "1") (pinfunction "CE_1") (pintype "bidirectional"))
    )
    (net (code "25") (name "DONE") (class "Default")
      (node (ref "U4") (pin "71") (pinfunction "DONE_2_71") (pintype "bidirectional"))
    )
    (net (code "26") (name "FPGA_GPIO_0") (class "Default")
      (node (ref "J5") (pin "10") (pinfunction "10_10") (pintype "bidirectional"))
      (node (ref "U4") (pin "1") (pinfunction "IO_L83N_VREF_3_1") (pintype "bidirectional"))
    )
    (net (code "27") (name "FPGA_GPIO_1") (class "Default")
      (node (ref "J5") (pin "1") (pinfunction "1_1") (pintype "bidirectional"))
      (node (ref "U4") (pin "2") (pinfunction "IO_L83P_3_2") (pintype "bidirectional"))
    )
    (net (code "28") (name "FPGA_GPIO_2") (class "Default")
      (node (ref "J5") (pin "9") (pinfunction "9_9") (pintype "bidirectional"))
      (node (ref "U4") (pin "5") (pinfunction "IO_L52N_3_5") (pintype "bidirectional"))
    )
    (net (code "29") (name "FPGA_GPIO_3") (class "Default")
      (node (ref "J5") (pin "2") (pinfunction "2_2") (pintype "bidirectional"))
      (node (ref "U4") (pin "6") (pinfunction "IO_L52P_3_6") (pintype "bidirectional"))
    )
    (net (code "30") (name "FPGA_GPIO_4") (class "Default")
      (node (ref "J5") (pin "8") (pinfunction "8_8") (pintype "bidirectional"))
      (node (ref "U4") (pin "7") (pinfunction "IO_L51N_3_7") (pintype "bidirectional"))
    )
    (net (code "31") (name "FPGA_GPIO_5") (class "Default")
      (node (ref "J5") (pin "3") (pinfunction "3_3") (pintype "bidirectional"))
      (node (ref "U4") (pin "8") (pinfunction "IO_L51P_3_8") (pintype "bidirectional"))
    )
    (net (code "32") (name "FPGA_GPIO_6") (class "Default")
      (node (ref "J5") (pin "7") (pinfunction "7_7") (pintype "bidirectional"))
      (node (ref "U4") (pin "9") (pinfunction "IO_L50N_3_9") (pintype "bidirectional"))
    )
    (net (code "33") (name "FPGA_GPIO_7") (class "Default")
      (node (ref "J5") (pin "4") (pinfunction "4_4") (pintype "bidirectional"))
      (node (ref "U4") (pin "10") (pinfunction "IO_L50P_3_10") (pintype "bidirectional"))
    )
    (net (code "34") (name "FPGA_GPIO_8") (class "Default")
      (node (ref "J5") (pin "6") (pinfunction "6_6") (pintype "bidirectional"))
      (node (ref "U4") (pin "11") (pinfunction "IO_L49N_3_11") (pintype "bidirectional"))
    )
    (net (code "35") (name "FPGA_GPIO_9") (class "Default")
      (node (ref "J5") (pin "5") (pinfunction "5_5") (pintype "bidirectional"))
      (node (ref "U4") (pin "12") (pinfunction "IO_L49P_3_12") (pintype "bidirectional"))
    )
    (net (code "36") (name "FPGA_GPIO_10") (class "Default")
      (node (ref "J6") (pin "5") (pinfunction "5_5") (pintype "bidirectional"))
      (node (ref "U4") (pin "24") (pinfunction "IO_L41P_GCLK27_3_24") (pintype "bidirectional"))
    )
    (net (code "37") (name "FPGA_GPIO_11") (class "Default")
      (node (ref "J6") (pin "6") (pinfunction "6_6") (pintype "bidirectional"))
      (node (ref "U4") (pin "23") (pinfunction "IO_L41N_GCLK26_3_23") (pintype "bidirectional"))
    )
    (net (code "38") (name "FPGA_GPIO_12") (class "Default")
      (node (ref "J6") (pin "4") (pinfunction "4_4") (pintype "bidirectional"))
      (node (ref "U4") (pin "27") (pinfunction "IO_L37P_3_27") (pintype "bidirectional"))
    )
    (net (code "39") (name "FPGA_GPIO_13") (class "Default")
      (node (ref "J6") (pin "7") (pinfunction "7_7") (pintype "bidirectional"))
      (node (ref "U4") (pin "26") (pinfunction "IO_L37N_3_26") (pintype "bidirectional"))
    )
    (net (code "40") (name "FPGA_GPIO_14") (class "Default")
      (node (ref "J6") (pin "3") (pinfunction "3_3") (pintype "bidirectional"))
      (node (ref "U4") (pin "30") (pinfunction "IO_L36P_3_30") (pintype "bidirectional"))
    )
    (net (code "41") (name "FPGA_GPIO_15") (class "Default")
      (node (ref "J6") (pin "8") (pinfunction "8_8") (pintype "bidirectional"))
      (node (ref "U4") (pin "29") (pinfunction "IO_L36N_3_29") (pintype "bidirectional"))
    )
    (net (code "42") (name "FPGA_GPIO_16") (class "Default")
      (node (ref "J6") (pin "2") (pinfunction "2_2") (pintype "bidirectional"))
      (node (ref "U4") (pin "33") (pinfunction "IO_L2P_3_33") (pintype "bidirectional"))
    )
    (net (code "43") (name "FPGA_GPIO_17") (class "Default")
      (node (ref "J6") (pin "9") (pinfunction "9_9") (pintype "bidirectional"))
      (node (ref "U4") (pin "32") (pinfunction "IO_L2N_3_32") (pintype "bidirectional"))
    )
    (net (code "44") (name "FPGA_GPIO_18") (class "Default")
      (node (ref "J6") (pin "1") (pinfunction "1_1") (pintype "bidirectional"))
      (node (ref "U4") (pin "35") (pinfunction "IO_L1P_3_35") (pintype "bidirectional"))
    )
    (net (code "45") (name "FPGA_GPIO_19") (class "Default")
      (node (ref "J6") (pin "10") (pinfunction "10_10") (pintype "bidirectional"))
      (node (ref "U4") (pin "34") (pinfunction "IO_L1N_VREF_3_34") (pintype "bidirectional"))
    )
    (net (code "46") (name "FPGA_LED0") (class "Default")
      (node (ref "R8") (pin "1") (pinfunction "1_1") (pintype "bidirectional"))
      (node (ref "U4") (pin "144") (pinfunction "IO_L1P_HSWAPEN_0_144") (pintype "bidirectional"))
    )
    (net (code "47") (name "FPGA_LED1") (class "Default")
      (node (ref "R9") (pin "1") (pinfunction "1_1") (pintype "bidirectional"))
      (node (ref "U4") (pin "143") (pinfunction "IO_L1N_VREF_0_143") (pintype "bidirectional"))
    )
    (net (code "48") (name "FPGA_LED2") (class "Default")
      (node (ref "R10") (pin "1") (pinfunction "1_1") (pintype "bidirectional"))
      (node (ref "U4") (pin "142") (pinfunction "IO_L2P_0_142") (pintype "bidirectional"))
    )
    (net (code "49") (name "FPGA_LED3") (class "Default")
      (node (ref "R11") (pin "1") (pinfunction "1_1") (pintype "bidirectional"))
      (node (ref "U4") (pin "141") (pinfunction "IO_L2N_0_141") (pintype "bidirectional"))
    )
    (net (code "50") (name "FPGA_RESET") (class "Default")
      (node (ref "R15") (pin "1") (pinfunction "1_1") (pintype "bidirectional"))
      (node (ref "S2") (pin "2") (pinfunction "3_2") (pintype "bidirectional"))
      (node (ref "U1") (pin "16") (pinfunction "PB6_OC1B_16") (pintype "bidirectional"))
      (node (ref "U4") (pin "37") (pinfunction "PROGRAM_B_2_37") (pintype "bidirectional"))
    )
    (net (code "51") (name "FPGA_VCCAUX") (class "Default")
      (node (ref "C10") (pin "1") (pinfunction "P$1_1") (pintype "bidirectional"))
      (node (ref "C11") (pin "1") (pinfunction "P$1_1") (pintype "bidirectional"))
      (node (ref "C12") (pin "1") (pinfunction "P$1_1") (pintype "bidirectional"))
      (node (ref "C14") (pin "1") (pinfunction "P$1_1") (pintype "bidirectional"))
      (node (ref "C15") (pin "1") (pinfunction "P$1_1") (pintype "bidirectional"))
      (node (ref "C16") (pin "1") (pinfunction "P$1_1") (pintype "bidirectional"))
      (node (ref "C17") (pin "1") (pinfunction "P$1_1") (pintype "bidirectional"))
      (node (ref "C18") (pin "1") (pinfunction "P$1_1") (pintype "bidirectional"))
      (node (ref "C19") (pin "1") (pinfunction "P$1_1") (pintype "bidirectional"))
      (node (ref "C2") (pin "1") (pinfunction "P$1_1") (pintype "bidirectional"))
      (node (ref "C20") (pin "1") (pinfunction "P$1_1") (pintype "bidirectional"))
      (node (ref "C21") (pin "1") (pinfunction "P$1_1") (pintype "bidirectional"))
      (node (ref "C22") (pin "1") (pinfunction "P$1_1") (pintype "bidirectional"))
      (node (ref "C23") (pin "1") (pinfunction "P$1_1") (pintype "bidirectional"))
      (node (ref "C24") (pin "1") (pinfunction "P$1_1") (pintype "bidirectional"))
      (node (ref "C3") (pin "1") (pinfunction "P$1_1") (pintype "bidirectional"))
      (node (ref "C4") (pin "2") (pinfunction "P$2_2") (pintype "bidirectional"))
      (node (ref "C6") (pin "1") (pinfunction "P$1_1") (pintype "bidirectional"))
      (node (ref "C7") (pin "1") (pinfunction "P$1_1") (pintype "bidirectional"))
      (node (ref "C8") (pin "1") (pinfunction "P$1_1") (pintype "bidirectional"))
      (node (ref "J3") (pin "1") (pinfunction "1_1") (pintype "bidirectional"))
      (node (ref "R12") (pin "1") (pinfunction "1_1") (pintype "bidirectional"))
      (node (ref "R13") (pin "1") (pinfunction "1_1") (pintype "bidirectional"))
      (node (ref "R14") (pin "1") (pinfunction "1_1") (pintype "bidirectional"))
      (node (ref "R15") (pin "2") (pinfunction "2_2") (pintype "bidirectional"))
      (node (ref "R19") (pin "1") (pinfunction "1_1") (pintype "bidirectional"))
      (node (ref "U4") (pin "103") (pinfunction "VCCO_1_103") (pintype "bidirectional"))
      (node (ref "U4") (pin "122") (pinfunction "VCCO_0_122") (pintype "bidirectional"))
      (node (ref "U4") (pin "125") (pinfunction "VCCO_0_125") (pintype "bidirectional"))
      (node (ref "U4") (pin "129") (pinfunction "VCCAUX_129") (pintype "bidirectional"))
      (node (ref "U4") (pin "135") (pinfunction "VCCO_0_135") (pintype "bidirectional"))
      (node (ref "U4") (pin "18") (pinfunction "VCCO_3_18") (pintype "bidirectional"))
      (node (ref "U4") (pin "20") (pinfunction "VCCAUX_20") (pintype "bidirectional"))
      (node (ref "U4") (pin "31") (pinfunction "VCCO_3_31") (pintype "bidirectional"))
      (node (ref "U4") (pin "36") (pinfunction "VCCAUX_36") (pintype "bidirectional"))
      (node (ref "U4") (pin "4") (pinfunction "VCCO_3_4") (pintype "bidirectional"))
      (node (ref "U4") (pin "42") (pinfunction "VCCO_2_42") (pintype "bidirectional"))
      (node (ref "U4") (pin "53") (pinfunction "VCCAUX_53") (pintype "bidirectional"))
      (node (ref "U4") (pin "63") (pinfunction "VCCO_2_63") (pintype "bidirectional"))
      (node (ref "U4") (pin "76") (pinfunction "VCCO_1_76") (pintype "bidirectional"))
      (node (ref "U4") (pin "86") (pinfunction "VCCO_1_86") (pintype "bidirectional"))
      (node (ref "U4") (pin "90") (pinfunction "VCCAUX_90") (pintype "bidirectional"))
      (node (ref "U5") (pin "8") (pinfunction "VDD_8") (pintype "bidirectional"))
      (node (ref "U7") (pin "2") (pinfunction "SENSE1-_2") (pintype "bidirectional"))
      (node (ref "X2") (pin "1") (pinfunction "EN_1") (pintype "bidirectional"))
      (node (ref "X2") (pin "4") (pinfunction "VS+_4") (pintype "bidirectional"))
      (node (ref "X3") (pin "1") (pinfunction "EN_1") (pintype "bidirectional"))
      (node (ref "X3") (pin "4") (pinfunction "VS+_4") (pintype "bidirectional"))
    )
    (net (code "52") (name "FPGA_VCCINT") (class "Default")
      (node (ref "C1") (pin "1") (pinfunction "P$1_1") (pintype "bidirectional"))
      (node (ref "C13") (pin "1") (pinfunction "P$1_1") (pintype "bidirectional"))
      (node (ref "C5") (pin "1") (pinfunction "P$1_1") (pintype "bidirectional"))
      (node (ref "C9") (pin "1") (pinfunction "P$1_1") (pintype "bidirectional"))
      (node (ref "J4") (pin "1") (pinfunction "1_1") (pintype "bidirectional"))
      (node (ref "R17") (pin "1") (pinfunction "1_1") (pintype "bidirectional"))
      (node (ref "U4") (pin "128") (pinfunction "VCCINT_128") (pintype "bidirectional"))
      (node (ref "U4") (pin "19") (pinfunction "VCCINT_19") (pintype "bidirectional"))
      (node (ref "U4") (pin "28") (pinfunction "VCCINT_28") (pintype "bidirectional"))
      (node (ref "U4") (pin "52") (pinfunction "VCCINT_52") (pintype "bidirectional"))
      (node (ref "U4") (pin "89") (pinfunction "VCCINT_89") (pintype "bidirectional"))
      (node (ref "U7") (pin "4") (pinfunction "SENSE2-_4") (pintype "bidirectional"))
    )
    (net (code "53") (name "GND") (class "Default")
      (node (ref "C1") (pin "2") (pinfunction "P$2_2") (pintype "bidirectional"))
      (node (ref "C10") (pin "2") (pinfunction "P$2_2") (pintype "bidirectional"))
      (node (ref "C11") (pin "2") (pinfunction "P$2_2") (pintype "bidirectional"))
      (node (ref "C12") (pin "2") (pinfunction "P$2_2") (pintype "bidirectional"))
      (node (ref "C13") (pin "2") (pinfunction "P$2_2") (pintype "bidirectional"))
      (node (ref "C14") (pin "2") (pinfunction "P$2_2") (pintype "bidirectional"))
      (node (ref "C15") (pin "2") (pinfunction "P$2_2") (pintype "bidirectional"))
      (node (ref "C16") (pin "2") (pinfunction "P$2_2") (pintype "bidirectional"))
      (node (ref "C17") (pin "2") (pinfunction "P$2_2") (pintype "bidirectional"))
      (node (ref "C18") (pin "2") (pinfunction "P$2_2") (pintype "bidirectional"))
      (node (ref "C19") (pin "2") (pinfunction "P$2_2") (pintype "bidirectional"))
      (node (ref "C2") (pin "2") (pinfunction "P$2_2") (pintype "bidirectional"))
      (node (ref "C20") (pin "2") (pinfunction "P$2_2") (pintype "bidirectional"))
      (node (ref "C21") (pin "2") (pinfunction "P$2_2") (pintype "bidirectional"))
      (node (ref "C22") (pin "2") (pinfunction "P$2_2") (pintype "bidirectional"))
      (node (ref "C23") (pin "2") (pinfunction "P$2_2") (pintype "bidirectional"))
      (node (ref "C24") (pin "2") (pinfunction "P$2_2") (pintype "bidirectional"))
      (node (ref "C25") (pin "2") (pinfunction "P$2_2") (pintype "bidirectional"))
      (node (ref "C26") (pin "1") (pinfunction "P$1_1") (pintype "bidirectional"))
      (node (ref "C27") (pin "1") (pinfunction "P$1_1") (pintype "bidirectional"))
      (node (ref "C28") (pin "2") (pinfunction "P$2_2") (pintype "bidirectional"))
      (node (ref "C29") (pin "2") (pinfunction "P$2_2") (pintype "bidirectional"))
      (node (ref "C3") (pin "2") (pinfunction "P$2_2") (pintype "bidirectional"))
      (node (ref "C30") (pin "2") (pinfunction "P$2_2") (pintype "bidirectional"))
      (node (ref "C31") (pin "1") (pinfunction "P$1_1") (pintype "bidirectional"))
      (node (ref "C4") (pin "1") (pinfunction "P$1_1") (pintype "bidirectional"))
      (node (ref "C5") (pin "2") (pinfunction "P$2_2") (pintype "bidirectional"))
      (node (ref "C6") (pin "2") (pinfunction "P$2_2") (pintype "bidirectional"))
      (node (ref "C7") (pin "2") (pinfunction "P$2_2") (pintype "bidirectional"))
      (node (ref "C8") (pin "2") (pinfunction "P$2_2") (pintype "bidirectional"))
      (node (ref "C9") (pin "2") (pinfunction "P$2_2") (pintype "bidirectional"))
      (node (ref "J1") (pin "6") (pinfunction "GND_6") (pintype "bidirectional"))
      (node (ref "J3") (pin "3") (pinfunction "2_3") (pintype "bidirectional"))
      (node (ref "J4") (pin "3") (pinfunction "2_3") (pintype "bidirectional"))
      (node (ref "J7") (pin "P$2") (pinfunction "GND_P$2") (pintype "bidirectional"))
      (node (ref "J8") (pin "5") (pinfunction "GND_5") (pintype "bidirectional"))
      (node (ref "LED0") (pin "2") (pinfunction "2_2") (pintype "bidirectional"))
      (node (ref "LED1") (pin "2") (pinfunction "2_2") (pintype "bidirectional"))
      (node (ref "LED2") (pin "2") (pinfunction "2_2") (pintype "bidirectional"))
      (node (ref "LED3") (pin "2") (pinfunction "2_2") (pintype "bidirectional"))
      (node (ref "LED4") (pin "2") (pinfunction "2_2") (pintype "bidirectional"))
      (node (ref "LED5") (pin "2") (pinfunction "2_2") (pintype "bidirectional"))
      (node (ref "LED6") (pin "2") (pinfunction "2_2") (pintype "bidirectional"))
      (node (ref "LED7") (pin "2") (pinfunction "2_2") (pintype "bidirectional"))
      (node (ref "R20") (pin "1") (pinfunction "1_1") (pintype "bidirectional"))
      (node (ref "R21") (pin "1") (pinfunction "1_1") (pintype "bidirectional"))
      (node (ref "R23") (pin "1") (pinfunction "1_1") (pintype "bidirectional"))
      (node (ref "R29") (pin "2") (pinfunction "2_2") (pintype "bidirectional"))
      (node (ref "R30") (pin "1") (pinfunction "1_1") (pintype "bidirectional"))
      (node (ref "R32") (pin "1") (pinfunction "1_1") (pintype "bidirectional"))
      (node (ref "S1") (pin "1") (pinfunction "1_1") (pintype "bidirectional"))
      (node (ref "S2") (pin "1") (pinfunction "1_1") (pintype "bidirectional"))
      (node (ref "S3") (pin "3") (pinfunction "2Y_3") (pintype "bidirectional"))
      (node (ref "S3") (pin "4") (pinfunction "1Y_4") (pintype "bidirectional"))
      (node (ref "U1") (pin "22") (pinfunction "GND_22") (pintype "bidirectional"))
      (node (ref "U1") (pin "53") (pinfunction "GND_53") (pintype "bidirectional"))
      (node (ref "U1") (pin "63") (pinfunction "GND_63") (pintype "bidirectional"))
      (node (ref "U1") (pin "PAD") (pinfunction "GND_PAD") (pintype "bidirectional"))
      (node (ref "U1") (pin "VIA1") (pinfunction "GND_VIA1") (pintype "bidirectional"))
      (node (ref "U1") (pin "VIA2") (pinfunction "GND_VIA2") (pintype "bidirectional"))
      (node (ref "U1") (pin "VIA3") (pinfunction "GND_VIA3") (pintype "bidirectional"))
      (node (ref "U1") (pin "VIA4") (pinfunction "GND_VIA4") (pintype "bidirectional"))
      (node (ref "U1") (pin "VIA5") (pinfunction "GND_VIA5") (pintype "bidirectional"))
      (node (ref "U1") (pin "VIA6") (pinfunction "GND_VIA6") (pintype "bidirectional"))
      (node (ref "U1") (pin "VIA7") (pinfunction "GND_VIA7") (pintype "bidirectional"))
      (node (ref "U1") (pin "VIA8") (pinfunction "GND_VIA8") (pintype "bidirectional"))
      (node (ref "U1") (pin "VIA9") (pinfunction "GND_VIA9") (pintype "bidirectional"))
      (node (ref "U10") (pin "9") (pinfunction "GND_9") (pintype "bidirectional"))
      (node (ref "U2") (pin "4") (pinfunction "VSS_4") (pintype "bidirectional"))
      (node (ref "U3") (pin "1") (pinfunction "GND_1") (pintype "bidirectional"))
      (node (ref "U3") (pin "11") (pinfunction "GND_11") (pintype "bidirectional"))
      (node (ref "U3") (pin "12") (pinfunction "GND_12") (pintype "bidirectional"))
      (node (ref "U4") (pin "108") (pinfunction "GND_108") (pintype "bidirectional"))
      (node (ref "U4") (pin "113") (pinfunction "GND_113") (pintype "bidirectional"))
      (node (ref "U4") (pin "13") (pinfunction "GND_13") (pintype "bidirectional"))
      (node (ref "U4") (pin "130") (pinfunction "GND_130") (pintype "bidirectional"))
      (node (ref "U4") (pin "136") (pinfunction "GND_136") (pintype "bidirectional"))
      (node (ref "U4") (pin "25") (pinfunction "GND_25") (pintype "bidirectional"))
      (node (ref "U4") (pin "3") (pinfunction "GND_3") (pintype "bidirectional"))
      (node (ref "U4") (pin "47") (pinfunction "IO_L48N_RDWR_B_VREF_2_47") (pintype "bidirectional"))
      (node (ref "U4") (pin "49") (pinfunction "GND_49") (pintype "bidirectional"))
      (node (ref "U4") (pin "54") (pinfunction "GND_54") (pintype "bidirectional"))
      (node (ref "U4") (pin "68") (pinfunction "GND_68") (pintype "bidirectional"))
      (node (ref "U4") (pin "77") (pinfunction "GND_77") (pintype "bidirectional"))
      (node (ref "U4") (pin "91") (pinfunction "GND_91") (pintype "bidirectional"))
      (node (ref "U4") (pin "96") (pinfunction "GND_96") (pintype "bidirectional"))
      (node (ref "U5") (pin "4") (pinfunction "VSS_4") (pintype "bidirectional"))
      (node (ref "U6") (pin "5") (pinfunction "GND_5") (pintype "bidirectional"))
      (node (ref "U6") (pin "P$1") (pinfunction "GND_P$1") (pintype "bidirectional"))
      (node (ref "U6") (pin "P$2") (pinfunction "GND_P$2") (pintype "bidirectional"))
      (node (ref "U6") (pin "P$3") (pinfunction "GND_P$3") (pintype "bidirectional"))
      (node (ref "U6") (pin "P$4") (pinfunction "GND_P$4") (pintype "bidirectional"))
      (node (ref "U7") (pin "5") (pinfunction "GND_5") (pintype "bidirectional"))
      (node (ref "U7") (pin "P$1") (pinfunction "GND_P$1") (pintype "bidirectional"))
      (node (ref "U7") (pin "P$2") (pinfunction "GND_P$2") (pintype "bidirectional"))
      (node (ref "U7") (pin "P$3") (pinfunction "GND_P$3") (pintype "bidirectional"))
      (node (ref "U7") (pin "P$4") (pinfunction "GND_P$4") (pintype "bidirectional"))
      (node (ref "U8") (pin "5") (pinfunction "GND_5") (pintype "bidirectional"))
      (node (ref "U8") (pin "P$1") (pinfunction "GND_P$1") (pintype "bidirectional"))
      (node (ref "U8") (pin "P$2") (pinfunction "GND_P$2") (pintype "bidirectional"))
      (node (ref "U8") (pin "P$3") (pinfunction "GND_P$3") (pintype "bidirectional"))
      (node (ref "U8") (pin "P$4") (pinfunction "GND_P$4") (pintype "bidirectional"))
      (node (ref "U9") (pin "18") (pinfunction "GND_18") (pintype "bidirectional"))
      (node (ref "U9") (pin "21") (pinfunction "GND_21") (pintype "bidirectional"))
      (node (ref "U9") (pin "25") (pinfunction "AGND_25") (pintype "bidirectional"))
      (node (ref "U9") (pin "26") (pinfunction "TEST_26") (pintype "bidirectional"))
      (node (ref "U9") (pin "7") (pinfunction "GND_7") (pintype "bidirectional"))
      (node (ref "X2") (pin "2") (pinfunction "GND_2") (pintype "bidirectional"))
      (node (ref "X3") (pin "2") (pinfunction "GND_2") (pintype "bidirectional"))
    )
    (net (code "54") (name "INIT_B") (class "Default")
      (node (ref "U1") (pin "17") (pinfunction "PB7_OC2/OC1C_17") (pintype "bidirectional"))
      (node (ref "U4") (pin "39") (pinfunction "IO_L65P_INIT_B_2_39") (pintype "bidirectional"))
    )
    (net (code "55") (name "JTAG_TCK") (class "Default")
      (node (ref "J7") (pin "P$3") (pinfunction "TCK_P$3") (pintype "bidirectional"))
      (node (ref "U1") (pin "57") (pinfunction "PF4_ADC4/TCK_57") (pintype "bidirectional"))
      (node (ref "U4") (pin "109") (pinfunction "TCK_109") (pintype "bidirectional"))
    )
    (net (code "56") (name "JTAG_TDI") (class "Default")
      (node (ref "J7") (pin "P$5") (pinfunction "TDI_P$5") (pintype "bidirectional"))
      (node (ref "U1") (pin "55") (pinfunction "PF6_ADC6/TDO_55") (pintype "bidirectional"))
      (node (ref "U4") (pin "110") (pinfunction "TDI_110") (pintype "bidirectional"))
    )
    (net (code "57") (name "JTAG_TDO") (class "Default")
      (node (ref "J7") (pin "P$4") (pinfunction "TDO_P$4") (pintype "bidirectional"))
      (node (ref "U1") (pin "56") (pinfunction "PF5_ADC5/TMS_56") (pintype "bidirectional"))
      (node (ref "U4") (pin "106") (pinfunction "TDO_106") (pintype "bidirectional"))
    )
    (net (code "58") (name "JTAG_TMS") (class "Default")
      (node (ref "J7") (pin "P$6") (pinfunction "TMS_P$6") (pintype "bidirectional"))
      (node (ref "U1") (pin "54") (pinfunction "PF7_ADC7/TDI_54") (pintype "bidirectional"))
      (node (ref "U4") (pin "107") (pinfunction "TMS_107") (pintype "bidirectional"))
    )
    (net (code "59") (name "MCU_FLASH_CE") (class "Default")
      (node (ref "R2") (pin "2") (pinfunction "2_2") (pintype "bidirectional"))
      (node (ref "U1") (pin "14") (pinfunction "PB4_OC0_14") (pintype "bidirectional"))
      (node (ref "U2") (pin "1") (pinfunction "CE_1") (pintype "bidirectional"))
    )
    (net (code "60") (name "MCU_GPIO_0") (class "Default")
      (node (ref "J2") (pin "4") (pinfunction "4_4") (pintype "bidirectional"))
      (node (ref "U1") (pin "58") (pinfunction "PF3_ADC3_58") (pintype "bidirectional"))
    )
    (net (code "61") (name "MCU_GPIO_1") (class "Default")
      (node (ref "J2") (pin "3") (pinfunction "3_3") (pintype "bidirectional"))
      (node (ref "U1") (pin "59") (pinfunction "PF2_ADC2_59") (pintype "bidirectional"))
    )
    (net (code "62") (name "MCU_GPIO_2") (class "Default")
      (node (ref "J2") (pin "2") (pinfunction "2_2") (pintype "bidirectional"))
      (node (ref "U1") (pin "60") (pinfunction "PF1_ADC1_60") (pintype "bidirectional"))
    )
    (net (code "63") (name "MCU_GPIO_3") (class "Default")
      (node (ref "J2") (pin "1") (pinfunction "1_1") (pintype "bidirectional"))
      (node (ref "U1") (pin "61") (pinfunction "PF0_ADC0_61") (pintype "bidirectional"))
    )
    (net (code "64") (name "MCU_LED0") (class "Default")
      (node (ref "R3") (pin "1") (pinfunction "1_1") (pintype "bidirectional"))
      (node (ref "U1") (pin "15") (pinfunction "PB5_OC1A_15") (pintype "bidirectional"))
    )
    (net (code "65") (name "MCU_LED1") (class "Default")
      (node (ref "R4") (pin "1") (pinfunction "1_1") (pintype "bidirectional"))
      (node (ref "U1") (pin "10") (pinfunction "PB0_SS#_10") (pintype "bidirectional"))
    )
    (net (code "66") (name "MCU_LED2") (class "Default")
      (node (ref "R5") (pin "1") (pinfunction "1_1") (pintype "bidirectional"))
      (node (ref "U1") (pin "4") (pinfunction "PE2_XCK0/AIN0_4") (pintype "bidirectional"))
    )
    (net (code "67") (name "MCU_LED3") (class "Default")
      (node (ref "R6") (pin "1") (pinfunction "1_1") (pintype "bidirectional"))
      (node (ref "U1") (pin "5") (pinfunction "PE3_OC3A/AIN1_5") (pintype "bidirectional"))
    )
    (net (code "68") (name "MCU_MISO") (class "Default")
      (node (ref "U1") (pin "13") (pinfunction "PB3_MISO_13") (pintype "bidirectional"))
      (node (ref "U2") (pin "2") (pinfunction "SO_2") (pintype "bidirectional"))
      (node (ref "U3") (pin "7") (pinfunction "SDO_7") (pintype "bidirectional"))
    )
    (net (code "69") (name "MCU_MOSI") (class "Default")
      (node (ref "U1") (pin "12") (pinfunction "PB2_MOSI_12") (pintype "bidirectional"))
      (node (ref "U2") (pin "5") (pinfunction "SI_5") (pintype "bidirectional"))
      (node (ref "U3") (pin "5") (pinfunction "SDI_5") (pintype "bidirectional"))
    )
    (net (code "70") (name "MCU_RESET") (class "Default")
      (node (ref "J1") (pin "5") (pinfunction "RST_5") (pintype "bidirectional"))
      (node (ref "R7") (pin "1") (pinfunction "1_1") (pintype "bidirectional"))
      (node (ref "S1") (pin "2") (pinfunction "3_2") (pintype "bidirectional"))
      (node (ref "U1") (pin "20") (pinfunction "_RESET_20") (pintype "bidirectional"))
    )
    (net (code "71") (name "MCU_RX0{slash}PDI") (class "Default")
      (node (ref "J1") (pin "4") (pinfunction "MOSI_4") (pintype "bidirectional"))
      (node (ref "U1") (pin "2") (pinfunction "PE0_RXD0/PDI_2") (pintype "bidirectional"))
      (node (ref "U9") (pin "1") (pinfunction "TXD_1") (pintype "bidirectional"))
    )
    (net (code "72") (name "MCU_SCK") (class "Default")
      (node (ref "J1") (pin "3") (pinfunction "SCK_3") (pintype "bidirectional"))
      (node (ref "U1") (pin "11") (pinfunction "PB1_SCK_11") (pintype "bidirectional"))
      (node (ref "U2") (pin "6") (pinfunction "SCK_6") (pintype "bidirectional"))
      (node (ref "U3") (pin "6") (pinfunction "SCK_6") (pintype "bidirectional"))
    )
    (net (code "73") (name "MCU_TX0{slash}PDO") (class "Default")
      (node (ref "J1") (pin "1") (pinfunction "MISO_1") (pintype "bidirectional"))
      (node (ref "U1") (pin "3") (pinfunction "PE1_TXD0/PDO_3") (pintype "bidirectional"))
      (node (ref "U9") (pin "5") (pinfunction "RXD_5") (pintype "bidirectional"))
    )
    (net (code "74") (name "MCU_VCC") (class "Default")
      (node (ref "R1") (pin "1") (pinfunction "1_1") (pintype "bidirectional"))
      (node (ref "R2") (pin "1") (pinfunction "1_1") (pintype "bidirectional"))
      (node (ref "R22") (pin "1") (pinfunction "1_1") (pintype "bidirectional"))
      (node (ref "R7") (pin "2") (pinfunction "2_2") (pintype "bidirectional"))
      (node (ref "U1") (pin "21") (pinfunction "VCC_21") (pintype "bidirectional"))
      (node (ref "U1") (pin "52") (pinfunction "VCC_52") (pintype "bidirectional"))
      (node (ref "U1") (pin "62") (pinfunction "AVREF_62") (pintype "bidirectional"))
      (node (ref "U1") (pin "64") (pinfunction "AVCC_64") (pintype "bidirectional"))
      (node (ref "U2") (pin "3") (pinfunction "WP_3") (pintype "bidirectional"))
      (node (ref "U2") (pin "7") (pinfunction "HOLD_7") (pintype "bidirectional"))
      (node (ref "U2") (pin "8") (pinfunction "VDD_8") (pintype "bidirectional"))
      (node (ref "U8") (pin "4") (pinfunction "SENSE2-_4") (pintype "bidirectional"))
    )
    (net (code "75") (name "MODE0") (class "Default")
      (node (ref "R12") (pin "2") (pinfunction "2_2") (pintype "bidirectional"))
      (node (ref "S3") (pin "1") (pinfunction "1X_1") (pintype "bidirectional"))
      (node (ref "U4") (pin "69") (pinfunction "IO_L1N_M0_CMPMISO_2_69") (pintype "bidirectional"))
    )
    (net (code "76") (name "MODE1") (class "Default")
      (node (ref "R13") (pin "2") (pinfunction "2_2") (pintype "bidirectional"))
      (node (ref "S3") (pin "2") (pinfunction "2X_2") (pintype "bidirectional"))
      (node (ref "U4") (pin "60") (pinfunction "IO_L13P_M1_2_60") (pintype "bidirectional"))
    )
    (net (code "77") (name "N$4") (class "Default")
      (node (ref "U9") (pin "28") (pinfunction "OSCO_28") (pintype "bidirectional"))
    )
    (net (code "78") (name "N$5") (class "Default")
      (node (ref "U9") (pin "27") (pinfunction "OSCI_27") (pintype "bidirectional"))
    )
    (net (code "79") (name "N$6") (class "Default")
      (node (ref "U9") (pin "19") (pinfunction "RESET#_19") (pintype "bidirectional"))
    )
    (net (code "80") (name "N$12") (class "Default")
      (node (ref "U4") (pin "50") (pinfunction "IO_L31N_GCLK30_D15_2_50") (pintype "bidirectional"))
    )
    (net (code "81") (name "N$17") (class "Default")
      (node (ref "U9") (pin "3") (pinfunction "RTS#_3") (pintype "bidirectional"))
    )
    (net (code "82") (name "N$18") (class "Default")
      (node (ref "U9") (pin "11") (pinfunction "CTS#_11") (pintype "bidirectional"))
    )
    (net (code "83") (name "N$19") (class "Default")
      (node (ref "U9") (pin "2") (pinfunction "DTR#_2") (pintype "bidirectional"))
    )
    (net (code "84") (name "N$20") (class "Default")
      (node (ref "U9") (pin "9") (pinfunction "DSR#_9") (pintype "bidirectional"))
    )
    (net (code "85") (name "N$21") (class "Default")
      (node (ref "U9") (pin "10") (pinfunction "DCD#_10") (pintype "bidirectional"))
    )
    (net (code "86") (name "N$22") (class "Default")
      (node (ref "U9") (pin "6") (pinfunction "RI#_6") (pintype "bidirectional"))
    )
    (net (code "87") (name "N$26") (class "Default")
      (node (ref "U9") (pin "12") (pinfunction "CBUS4_12") (pintype "bidirectional"))
    )
    (net (code "88") (name "N$31") (class "Default")
      (node (ref "U4") (pin "140") (pinfunction "IO_L3P_0_140") (pintype "bidirectional"))
    )
    (net (code "89") (name "N$34") (class "Default")
      (node (ref "U4") (pin "87") (pinfunction "IO_L42N_GCLK6_TRDY1_1_87") (pintype "bidirectional"))
    )
    (net (code "90") (name "N$35") (class "Default")
      (node (ref "U4") (pin "88") (pinfunction "IO_L42P_GCLK7_1_88") (pintype "bidirectional"))
    )
    (net (code "91") (name "N$36") (class "Default")
      (node (ref "U4") (pin "92") (pinfunction "IO_L41N_GCLK8_1_92") (pintype "bidirectional"))
    )
    (net (code "92") (name "N$37") (class "Default")
      (node (ref "U4") (pin "93") (pinfunction "IO_L41P_GCLK9_IRDY1_1_93") (pintype "bidirectional"))
    )
    (net (code "93") (name "N$91") (class "Default")
      (node (ref "U4") (pin "57") (pinfunction "IO_L14N_D12_2_57") (pintype "bidirectional"))
    )
    (net (code "94") (name "N$93") (class "Default")
      (node (ref "U4") (pin "58") (pinfunction "IO_L14P_D11_2_58") (pintype "bidirectional"))
    )
    (net (code "95") (name "N$94") (class "Default")
      (node (ref "U4") (pin "59") (pinfunction "IO_L13N_D10_2_59") (pintype "bidirectional"))
    )
    (net (code "96") (name "N$96") (class "Default")
      (node (ref "U4") (pin "56") (pinfunction "IO_L30P_GCLK1_D13_2_56") (pintype "bidirectional"))
    )
    (net (code "97") (name "N$98") (class "Default")
      (node (ref "U4") (pin "41") (pinfunction "IO_L64P_D8_2_41") (pintype "bidirectional"))
    )
    (net (code "98") (name "N$941") (class "Default")
      (node (ref "U4") (pin "40") (pinfunction "IO_L64N_D9_2_40") (pintype "bidirectional"))
    )
    (net (code "99") (name "Net-(C28-P$1)") (class "Default")
      (node (ref "C28") (pin "1") (pinfunction "P$1_1") (pintype "bidirectional"))
      (node (ref "U9") (pin "17") (pinfunction "3V3OUT_17") (pintype "bidirectional"))
    )
    (net (code "100") (name "Net-(J8-D+)") (class "Default")
      (node (ref "J8") (pin "3") (pinfunction "D+_3") (pintype "bidirectional"))
      (node (ref "U9") (pin "15") (pinfunction "USBDP_15") (pintype "bidirectional"))
    )
    (net (code "101") (name "Net-(J8-D-)") (class "Default")
      (node (ref "J8") (pin "2") (pinfunction "D-_2") (pintype "bidirectional"))
      (node (ref "U9") (pin "16") (pinfunction "USBDM_16") (pintype "bidirectional"))
    )
    (net (code "102") (name "Net-(L2-P$2)") (class "Default")
      (node (ref "L2") (pin "2") (pinfunction "P$2_2") (pintype "bidirectional"))
      (node (ref "U10") (pin "4") (pinfunction "SW1_4") (pintype "bidirectional"))
    )
    (net (code "103") (name "Net-(L3-P$1)") (class "Default")
      (node (ref "L3") (pin "1") (pinfunction "P$1_1") (pintype "bidirectional"))
      (node (ref "U10") (pin "6") (pinfunction "SW2_6") (pintype "bidirectional"))
    )
    (net (code "104") (name "Net-(LED0-Pad1)") (class "Default")
      (node (ref "LED0") (pin "1") (pinfunction "1_1") (pintype "bidirectional"))
      (node (ref "R3") (pin "2") (pinfunction "2_2") (pintype "bidirectional"))
    )
    (net (code "105") (name "Net-(LED1-Pad1)") (class "Default")
      (node (ref "LED1") (pin "1") (pinfunction "1_1") (pintype "bidirectional"))
      (node (ref "R4") (pin "2") (pinfunction "2_2") (pintype "bidirectional"))
    )
    (net (code "106") (name "Net-(LED2-Pad1)") (class "Default")
      (node (ref "LED2") (pin "1") (pinfunction "1_1") (pintype "bidirectional"))
      (node (ref "R5") (pin "2") (pinfunction "2_2") (pintype "bidirectional"))
    )
    (net (code "107") (name "Net-(LED3-Pad1)") (class "Default")
      (node (ref "LED3") (pin "1") (pinfunction "1_1") (pintype "bidirectional"))
      (node (ref "R6") (pin "2") (pinfunction "2_2") (pintype "bidirectional"))
    )
    (net (code "108") (name "Net-(LED4-Pad1)") (class "Default")
      (node (ref "LED4") (pin "1") (pinfunction "1_1") (pintype "bidirectional"))
      (node (ref "R8") (pin "2") (pinfunction "2_2") (pintype "bidirectional"))
    )
    (net (code "109") (name "Net-(LED5-Pad1)") (class "Default")
      (node (ref "LED5") (pin "1") (pinfunction "1_1") (pintype "bidirectional"))
      (node (ref "R9") (pin "2") (pinfunction "2_2") (pintype "bidirectional"))
    )
    (net (code "110") (name "Net-(LED6-Pad1)") (class "Default")
      (node (ref "LED6") (pin "1") (pinfunction "1_1") (pintype "bidirectional"))
      (node (ref "R10") (pin "2") (pinfunction "2_2") (pintype "bidirectional"))
    )
    (net (code "111") (name "Net-(LED7-Pad1)") (class "Default")
      (node (ref "LED7") (pin "1") (pinfunction "1_1") (pintype "bidirectional"))
      (node (ref "R11") (pin "2") (pinfunction "2_2") (pintype "bidirectional"))
    )
    (net (code "112") (name "Net-(PWR-Pad2)") (class "Default")
      (node (ref "PWR") (pin "2") (pinfunction "2_2") (pintype "bidirectional"))
      (node (ref "R32") (pin "2") (pinfunction "2_2") (pintype "bidirectional"))
    )
    (net (code "113") (name "Net-(R26-Pad2)") (class "Default")
      (node (ref "R26") (pin "2") (pinfunction "2_2") (pintype "bidirectional"))
      (node (ref "TX") (pin "2") (pinfunction "2_2") (pintype "bidirectional"))
    )
    (net (code "114") (name "Net-(R27-Pad2)") (class "Default")
      (node (ref "R27") (pin "2") (pinfunction "2_2") (pintype "bidirectional"))
      (node (ref "RX") (pin "2") (pinfunction "2_2") (pintype "bidirectional"))
    )
    (net (code "115") (name "Net-(U1-XTAL1)") (class "Default")
      (node (ref "U1") (pin "24") (pinfunction "XTAL1_24") (pintype "bidirectional"))
      (node (ref "X1") (pin "3") (pinfunction "P$2_3") (pintype "bidirectional"))
    )
    (net (code "116") (name "Net-(U1-XTAL2)") (class "Default")
      (node (ref "U1") (pin "23") (pinfunction "XTAL2_23") (pintype "bidirectional"))
      (node (ref "X1") (pin "1") (pinfunction "P$1_1") (pintype "bidirectional"))
    )
    (net (code "117") (name "Net-(U6-ADDR_SEL)") (class "Default")
      (node (ref "R20") (pin "2") (pinfunction "2_2") (pintype "bidirectional"))
      (node (ref "U6") (pin "6") (pinfunction "ADDR_SEL_6") (pintype "bidirectional"))
    )
    (net (code "118") (name "Net-(U7-ADDR_SEL)") (class "Default")
      (node (ref "R21") (pin "2") (pinfunction "2_2") (pintype "bidirectional"))
      (node (ref "U7") (pin "6") (pinfunction "ADDR_SEL_6") (pintype "bidirectional"))
    )
    (net (code "119") (name "Net-(U8-ADDR_SEL)") (class "Default")
      (node (ref "R23") (pin "2") (pinfunction "2_2") (pintype "bidirectional"))
      (node (ref "U8") (pin "6") (pinfunction "ADDR_SEL_6") (pintype "bidirectional"))
    )
    (net (code "120") (name "Net-(U9-CBUS2)") (class "Default")
      (node (ref "R26") (pin "1") (pinfunction "1_1") (pintype "bidirectional"))
      (node (ref "U9") (pin "13") (pinfunction "CBUS2_13") (pintype "bidirectional"))
    )
    (net (code "121") (name "Net-(U9-CBUS3)") (class "Default")
      (node (ref "R27") (pin "1") (pinfunction "1_1") (pintype "bidirectional"))
      (node (ref "U9") (pin "14") (pinfunction "CBUS3_14") (pintype "bidirectional"))
    )
    (net (code "122") (name "Net-(U10-VFB1)") (class "Default")
      (node (ref "R28") (pin "2") (pinfunction "2_2") (pintype "bidirectional"))
      (node (ref "R29") (pin "1") (pinfunction "1_1") (pintype "bidirectional"))
      (node (ref "U10") (pin "1") (pinfunction "VFB1_1") (pintype "bidirectional"))
    )
    (net (code "123") (name "Net-(U10-VFB2)") (class "Default")
      (node (ref "R30") (pin "2") (pinfunction "2_2") (pintype "bidirectional"))
      (node (ref "R31") (pin "1") (pinfunction "1_1") (pintype "bidirectional"))
      (node (ref "U10") (pin "8") (pinfunction "VFB2_8") (pintype "bidirectional"))
    )
    (net (code "124") (name "OSC_32") (class "Default")
      (node (ref "U4") (pin "94") (pinfunction "IO_L40N_GCLK10_1_94") (pintype "bidirectional"))
      (node (ref "X3") (pin "3") (pinfunction "OUTPUT_3") (pintype "bidirectional"))
    )
    (net (code "125") (name "OSC_50") (class "Default")
      (node (ref "U4") (pin "51") (pinfunction "IO_L31P_GCLK31_D14_2_51") (pintype "bidirectional"))
      (node (ref "X2") (pin "3") (pinfunction "OUTPUT_3") (pintype "bidirectional"))
    )
    (net (code "126") (name "RD") (class "Default")
      (node (ref "U1") (pin "34") (pinfunction "PG1_RD#_34") (pintype "bidirectional"))
      (node (ref "U4") (pin "75") (pinfunction "IO_L74P_AWAKE_1_75") (pintype "bidirectional"))
    )
    (net (code "127") (name "SELECTMAP_D0{slash}FPGA_MISO1") (class "Default")
      (node (ref "U1") (pin "32") (pinfunction "PD7_T2_32") (pintype "bidirectional"))
      (node (ref "U4") (pin "65") (pinfunction "IO_L3P_D0_DIN_MISO_MISO1_2_65") (pintype "bidirectional"))
      (node (ref "U5") (pin "2") (pinfunction "SO_2") (pintype "bidirectional"))
    )
    (net (code "128") (name "SELECTMAP_D1{slash}FPGA_MISO2") (class "Default")
      (node (ref "U1") (pin "31") (pinfunction "PD6_T1_31") (pintype "bidirectional"))
      (node (ref "U4") (pin "62") (pinfunction "IO_L12P_D1_MISO2_2_62") (pintype "bidirectional"))
      (node (ref "U5") (pin "3") (pinfunction "WP_3") (pintype "bidirectional"))
    )
    (net (code "129") (name "SELECTMAP_D2{slash}FPGA_MISO3") (class "Default")
      (node (ref "U1") (pin "30") (pinfunction "PD5_XCK1_30") (pintype "bidirectional"))
      (node (ref "U4") (pin "61") (pinfunction "IO_L12N_D2_MISO3_2_61") (pintype "bidirectional"))
      (node (ref "U5") (pin "7") (pinfunction "HOLD_7") (pintype "bidirectional"))
    )
    (net (code "130") (name "SELECTMAP_D3") (class "Default")
      (node (ref "U1") (pin "29") (pinfunction "PD4_ICP1_29") (pintype "bidirectional"))
      (node (ref "U4") (pin "46") (pinfunction "IO_L49P_D3_2_46") (pintype "bidirectional"))
    )
    (net (code "131") (name "SELECTMAP_D4{slash}MCU_TX1") (class "Default")
      (node (ref "U1") (pin "28") (pinfunction "PD3_TXD1/INT3_28") (pintype "bidirectional"))
      (node (ref "U4") (pin "45") (pinfunction "IO_L49N_D4_2_45") (pintype "bidirectional"))
    )
    (net (code "132") (name "SELECTMAP_D5{slash}MCU_RX1") (class "Default")
      (node (ref "U1") (pin "27") (pinfunction "PD2_RXD1/INT2_27") (pintype "bidirectional"))
      (node (ref "U4") (pin "44") (pinfunction "IO_L62P_D5_2_44") (pintype "bidirectional"))
    )
    (net (code "133") (name "SELECTMAP_D6{slash}SDA") (class "Default")
      (node (ref "R25") (pin "1") (pinfunction "1_1") (pintype "bidirectional"))
      (node (ref "U1") (pin "26") (pinfunction "PD1_SDA/INT1_26") (pintype "bidirectional"))
      (node (ref "U4") (pin "43") (pinfunction "IO_L62N_D6_2_43") (pintype "bidirectional"))
      (node (ref "U6") (pin "8") (pinfunction "SMDATA_8") (pintype "bidirectional"))
      (node (ref "U7") (pin "8") (pinfunction "SMDATA_8") (pintype "bidirectional"))
      (node (ref "U8") (pin "8") (pinfunction "SMDATA_8") (pintype "bidirectional"))
    )
    (net (code "134") (name "SELECTMAP_D7{slash}SCL") (class "Default")
      (node (ref "R24") (pin "1") (pinfunction "1_1") (pintype "bidirectional"))
      (node (ref "U1") (pin "25") (pinfunction "PD0_SCL/INT0_25") (pintype "bidirectional"))
      (node (ref "U4") (pin "48") (pinfunction "IO_L48P_D7_2_48") (pintype "bidirectional"))
      (node (ref "U6") (pin "9") (pinfunction "SMCLK_9") (pintype "bidirectional"))
      (node (ref "U7") (pin "9") (pinfunction "SMCLK_9") (pintype "bidirectional"))
      (node (ref "U8") (pin "9") (pinfunction "SMCLK_9") (pintype "bidirectional"))
    )
    (net (code "135") (name "SUSPEND") (class "Default")
      (node (ref "U4") (pin "73") (pinfunction "SUSPEND_73") (pintype "bidirectional"))
    )
    (net (code "136") (name "USB_SHIELD") (class "Default")
      (node (ref "J8") (pin "CASE_1") (pinfunction "SHIELD_CASE_1") (pintype "bidirectional"))
    )
    (net (code "137") (name "USB_VCC") (class "Default")
      (node (ref "C26") (pin "2") (pinfunction "P$2_2") (pintype "bidirectional"))
      (node (ref "C27") (pin "2") (pinfunction "P$2_2") (pintype "bidirectional"))
      (node (ref "L1") (pin "2") (pinfunction "P$2_2") (pintype "bidirectional"))
      (node (ref "R18") (pin "1") (pinfunction "1_1") (pintype "bidirectional"))
      (node (ref "U6") (pin "1") (pinfunction "SENSE1+_1") (pintype "bidirectional"))
    )
    (net (code "138") (name "USB_VCC_RAW") (class "Default")
      (node (ref "C25") (pin "1") (pinfunction "P$1_1") (pintype "bidirectional"))
      (node (ref "J8") (pin "1") (pinfunction "VCC_1") (pintype "bidirectional"))
      (node (ref "L1") (pin "1") (pinfunction "P$1_1") (pintype "bidirectional"))
    )
    (net (code "139") (name "WIRELESS_CS") (class "Default")
      (node (ref "R1") (pin "2") (pinfunction "2_2") (pintype "bidirectional"))
      (node (ref "U1") (pin "6") (pinfunction "PE4_OC3B/INT4_6") (pintype "bidirectional"))
      (node (ref "U3") (pin "8") (pinfunction "_CS_8") (pintype "bidirectional"))
    )
    (net (code "140") (name "WIRELESS_INT") (class "Default")
      (node (ref "U1") (pin "9") (pinfunction "PE7_ICP3/INT7_9") (pintype "bidirectional"))
      (node (ref "U3") (pin "4") (pinfunction "INT_4") (pintype "bidirectional"))
    )
    (net (code "141") (name "WIRELESS_RESET") (class "Default")
      (node (ref "U1") (pin "7") (pinfunction "PE5_OC3C/INT5_7") (pintype "bidirectional"))
      (node (ref "U3") (pin "2") (pinfunction "_RESET_2") (pintype "bidirectional"))
    )
    (net (code "142") (name "WIRELESS_VCC") (class "Default")
      (node (ref "R16") (pin "1") (pinfunction "1_1") (pintype "bidirectional"))
      (node (ref "U3") (pin "10") (pinfunction "VI_10") (pintype "bidirectional"))
      (node (ref "U6") (pin "4") (pinfunction "SENSE2-_4") (pintype "bidirectional"))
    )
    (net (code "143") (name "WIRELESS_WAKE") (class "Default")
      (node (ref "U1") (pin "8") (pinfunction "PE6_T3/INT6_8") (pintype "bidirectional"))
      (node (ref "U3") (pin "3") (pinfunction "WAKE_3") (pintype "bidirectional"))
    )
    (net (code "144") (name "WR") (class "Default")
      (node (ref "U1") (pin "33") (pinfunction "PG0_WR#_33") (pintype "bidirectional"))
      (node (ref "U4") (pin "74") (pinfunction "IO_L74N_DOUT_BUSY_1_74") (pintype "bidirectional"))
    )
    (net (code "145") (name "unconnected-(U1-_PEN-Pad1)") (class "Default")
      (node (ref "U1") (pin "1") (pinfunction "_PEN_1") (pintype "bidirectional"))
    )
    (net (code "146") (name "unconnected-(U4-CMPCS_B_2-Pad72)") (class "Default")
      (node (ref "U4") (pin "72") (pinfunction "CMPCS_B_2_72") (pintype "bidirectional"))
    )
    (net (code "147") (name "unconnected-(U4-IO_L2N_CMPMOSI_2-Pad66)") (class "Default")
      (node (ref "U4") (pin "66") (pinfunction "IO_L2N_CMPMOSI_2_66") (pintype "bidirectional"))
    )
    (net (code "148") (name "unconnected-(U4-IO_L2P_CMPCLK_2-Pad67)") (class "Default")
      (node (ref "U4") (pin "67") (pinfunction "IO_L2P_CMPCLK_2_67") (pintype "bidirectional"))
    )
    (net (code "149") (name "unconnected-(U4-IO_L3N_0-Pad139)") (class "Default")
      (node (ref "U4") (pin "139") (pinfunction "IO_L3N_0_139") (pintype "bidirectional"))
    )
    (net (code "150") (name "unconnected-(U4-IO_L4N_0-Pad137)") (class "Default")
      (node (ref "U4") (pin "137") (pinfunction "IO_L4N_0_137") (pintype "bidirectional"))
    )
    (net (code "151") (name "unconnected-(U4-IO_L4P_0-Pad138)") (class "Default")
      (node (ref "U4") (pin "138") (pinfunction "IO_L4P_0_138") (pintype "bidirectional"))
    )
    (net (code "152") (name "unconnected-(U4-IO_L30N_GCLK0_USERCCLK_2-Pad55)") (class "Default")
      (node (ref "U4") (pin "55") (pinfunction "IO_L30N_GCLK0_USERCCLK_2_55") (pintype "bidirectional"))
    )
    (net (code "153") (name "unconnected-(U4-IO_L34N_GCLK18_0-Pad133)") (class "Default")
      (node (ref "U4") (pin "133") (pinfunction "IO_L34N_GCLK18_0_133") (pintype "bidirectional"))
    )
    (net (code "154") (name "unconnected-(U4-IO_L34P_GCLK19_0-Pad134)") (class "Default")
      (node (ref "U4") (pin "134") (pinfunction "IO_L34P_GCLK19_0_134") (pintype "bidirectional"))
    )
    (net (code "155") (name "unconnected-(U4-IO_L35N_GCLK16_0-Pad131)") (class "Default")
      (node (ref "U4") (pin "131") (pinfunction "IO_L35N_GCLK16_0_131") (pintype "bidirectional"))
    )
    (net (code "156") (name "unconnected-(U4-IO_L35P_GCLK17_0-Pad132)") (class "Default")
      (node (ref "U4") (pin "132") (pinfunction "IO_L35P_GCLK17_0_132") (pintype "bidirectional"))
    )
    (net (code "157") (name "unconnected-(U4-IO_L36N_GCLK14_0-Pad126)") (class "Default")
      (node (ref "U4") (pin "126") (pinfunction "IO_L36N_GCLK14_0_126") (pintype "bidirectional"))
    )
    (net (code "158") (name "unconnected-(U4-IO_L36P_GCLK15_0-Pad127)") (class "Default")
      (node (ref "U4") (pin "127") (pinfunction "IO_L36P_GCLK15_0_127") (pintype "bidirectional"))
    )
    (net (code "159") (name "unconnected-(U4-IO_L37N_GCLK12_0-Pad123)") (class "Default")
      (node (ref "U4") (pin "123") (pinfunction "IO_L37N_GCLK12_0_123") (pintype "bidirectional"))
    )
    (net (code "160") (name "unconnected-(U4-IO_L37P_GCLK13_0-Pad124)") (class "Default")
      (node (ref "U4") (pin "124") (pinfunction "IO_L37P_GCLK13_0_124") (pintype "bidirectional"))
    )
    (net (code "161") (name "unconnected-(U4-IO_L42N_GCLK24_3-Pad21)") (class "Default")
      (node (ref "U4") (pin "21") (pinfunction "IO_L42N_GCLK24_3_21") (pintype "bidirectional"))
    )
    (net (code "162") (name "unconnected-(U4-IO_L42P_GCLK25_TRDY2_3-Pad22)") (class "Default")
      (node (ref "U4") (pin "22") (pinfunction "IO_L42P_GCLK25_TRDY2_3_22") (pintype "bidirectional"))
    )
    (net (code "163") (name "unconnected-(U4-IO_L43N_GCLK22_IRDY2_3-Pad16)") (class "Default")
      (node (ref "U4") (pin "16") (pinfunction "IO_L43N_GCLK22_IRDY2_3_16") (pintype "bidirectional"))
    )
    (net (code "164") (name "unconnected-(U4-IO_L43P_GCLK23_3-Pad17)") (class "Default")
      (node (ref "U4") (pin "17") (pinfunction "IO_L43P_GCLK23_3_17") (pintype "bidirectional"))
    )
    (net (code "165") (name "unconnected-(U4-IO_L44N_GCLK20_3-Pad14)") (class "Default")
      (node (ref "U4") (pin "14") (pinfunction "IO_L44N_GCLK20_3_14") (pintype "bidirectional"))
    )
    (net (code "166") (name "unconnected-(U4-IO_L44P_GCLK21_3-Pad15)") (class "Default")
      (node (ref "U4") (pin "15") (pinfunction "IO_L44P_GCLK21_3_15") (pintype "bidirectional"))
    )
    (net (code "167") (name "unconnected-(U4-IO_L62N_VREF_0-Pad120)") (class "Default")
      (node (ref "U4") (pin "120") (pinfunction "IO_L62N_VREF_0_120") (pintype "bidirectional"))
    )
    (net (code "168") (name "unconnected-(U4-IO_L62P_0-Pad121)") (class "Default")
      (node (ref "U4") (pin "121") (pinfunction "IO_L62P_0_121") (pintype "bidirectional"))
    )
    (net (code "169") (name "unconnected-(U4-IO_L63N_SCP6_0-Pad118)") (class "Default")
      (node (ref "U4") (pin "118") (pinfunction "IO_L63N_SCP6_0_118") (pintype "bidirectional"))
    )
    (net (code "170") (name "unconnected-(U4-IO_L63P_SCP7_0-Pad119)") (class "Default")
      (node (ref "U4") (pin "119") (pinfunction "IO_L63P_SCP7_0_119") (pintype "bidirectional"))
    )
    (net (code "171") (name "unconnected-(U4-IO_L64N_SCP4_0-Pad116)") (class "Default")
      (node (ref "U4") (pin "116") (pinfunction "IO_L64N_SCP4_0_116") (pintype "bidirectional"))
    )
    (net (code "172") (name "unconnected-(U4-IO_L64P_SCP5_0-Pad117)") (class "Default")
      (node (ref "U4") (pin "117") (pinfunction "IO_L64P_SCP5_0_117") (pintype "bidirectional"))
    )
    (net (code "173") (name "unconnected-(U4-IO_L65N_SCP2_0-Pad114)") (class "Default")
      (node (ref "U4") (pin "114") (pinfunction "IO_L65N_SCP2_0_114") (pintype "bidirectional"))
    )
    (net (code "174") (name "unconnected-(U4-IO_L65P_SCP3_0-Pad115)") (class "Default")
      (node (ref "U4") (pin "115") (pinfunction "IO_L65P_SCP3_0_115") (pintype "bidirectional"))
    )
    (net (code "175") (name "unconnected-(U4-IO_L66N_SCP0_0-Pad111)") (class "Default")
      (node (ref "U4") (pin "111") (pinfunction "IO_L66N_SCP0_0_111") (pintype "bidirectional"))
    )
    (net (code "176") (name "unconnected-(U4-IO_L66P_SCP1_0-Pad112)") (class "Default")
      (node (ref "U4") (pin "112") (pinfunction "IO_L66P_SCP1_0_112") (pintype "bidirectional"))
    )
    (net (code "177") (name "unconnected-(U6-ALERT#-Pad7)") (class "Default")
      (node (ref "U6") (pin "7") (pinfunction "ALERT#_7") (pintype "bidirectional"))
    )
    (net (code "178") (name "unconnected-(U7-ALERT#-Pad7)") (class "Default")
      (node (ref "U7") (pin "7") (pinfunction "ALERT#_7") (pintype "bidirectional"))
    )
    (net (code "179") (name "unconnected-(U8-ALERT#-Pad7)") (class "Default")
      (node (ref "U8") (pin "7") (pinfunction "ALERT#_7") (pintype "bidirectional"))
    )
    (net (code "180") (name "unconnected-(U8-SENSE1+-Pad1)") (class "Default")
      (node (ref "U8") (pin "1") (pinfunction "SENSE1+_1") (pintype "bidirectional"))
    )
    (net (code "181") (name "unconnected-(U8-SENSE1--Pad2)") (class "Default")
      (node (ref "U8") (pin "2") (pinfunction "SENSE1-_2") (pintype "bidirectional"))
    )
    (net (code "182") (name "unconnected-(U9-CBUS1-Pad22)") (class "Default")
      (node (ref "U9") (pin "22") (pinfunction "CBUS1_22") (pintype "bidirectional"))
    )
  )
)
